# transponder-5_0.net
KiCad netlist of a schematic drawn in EAGLE
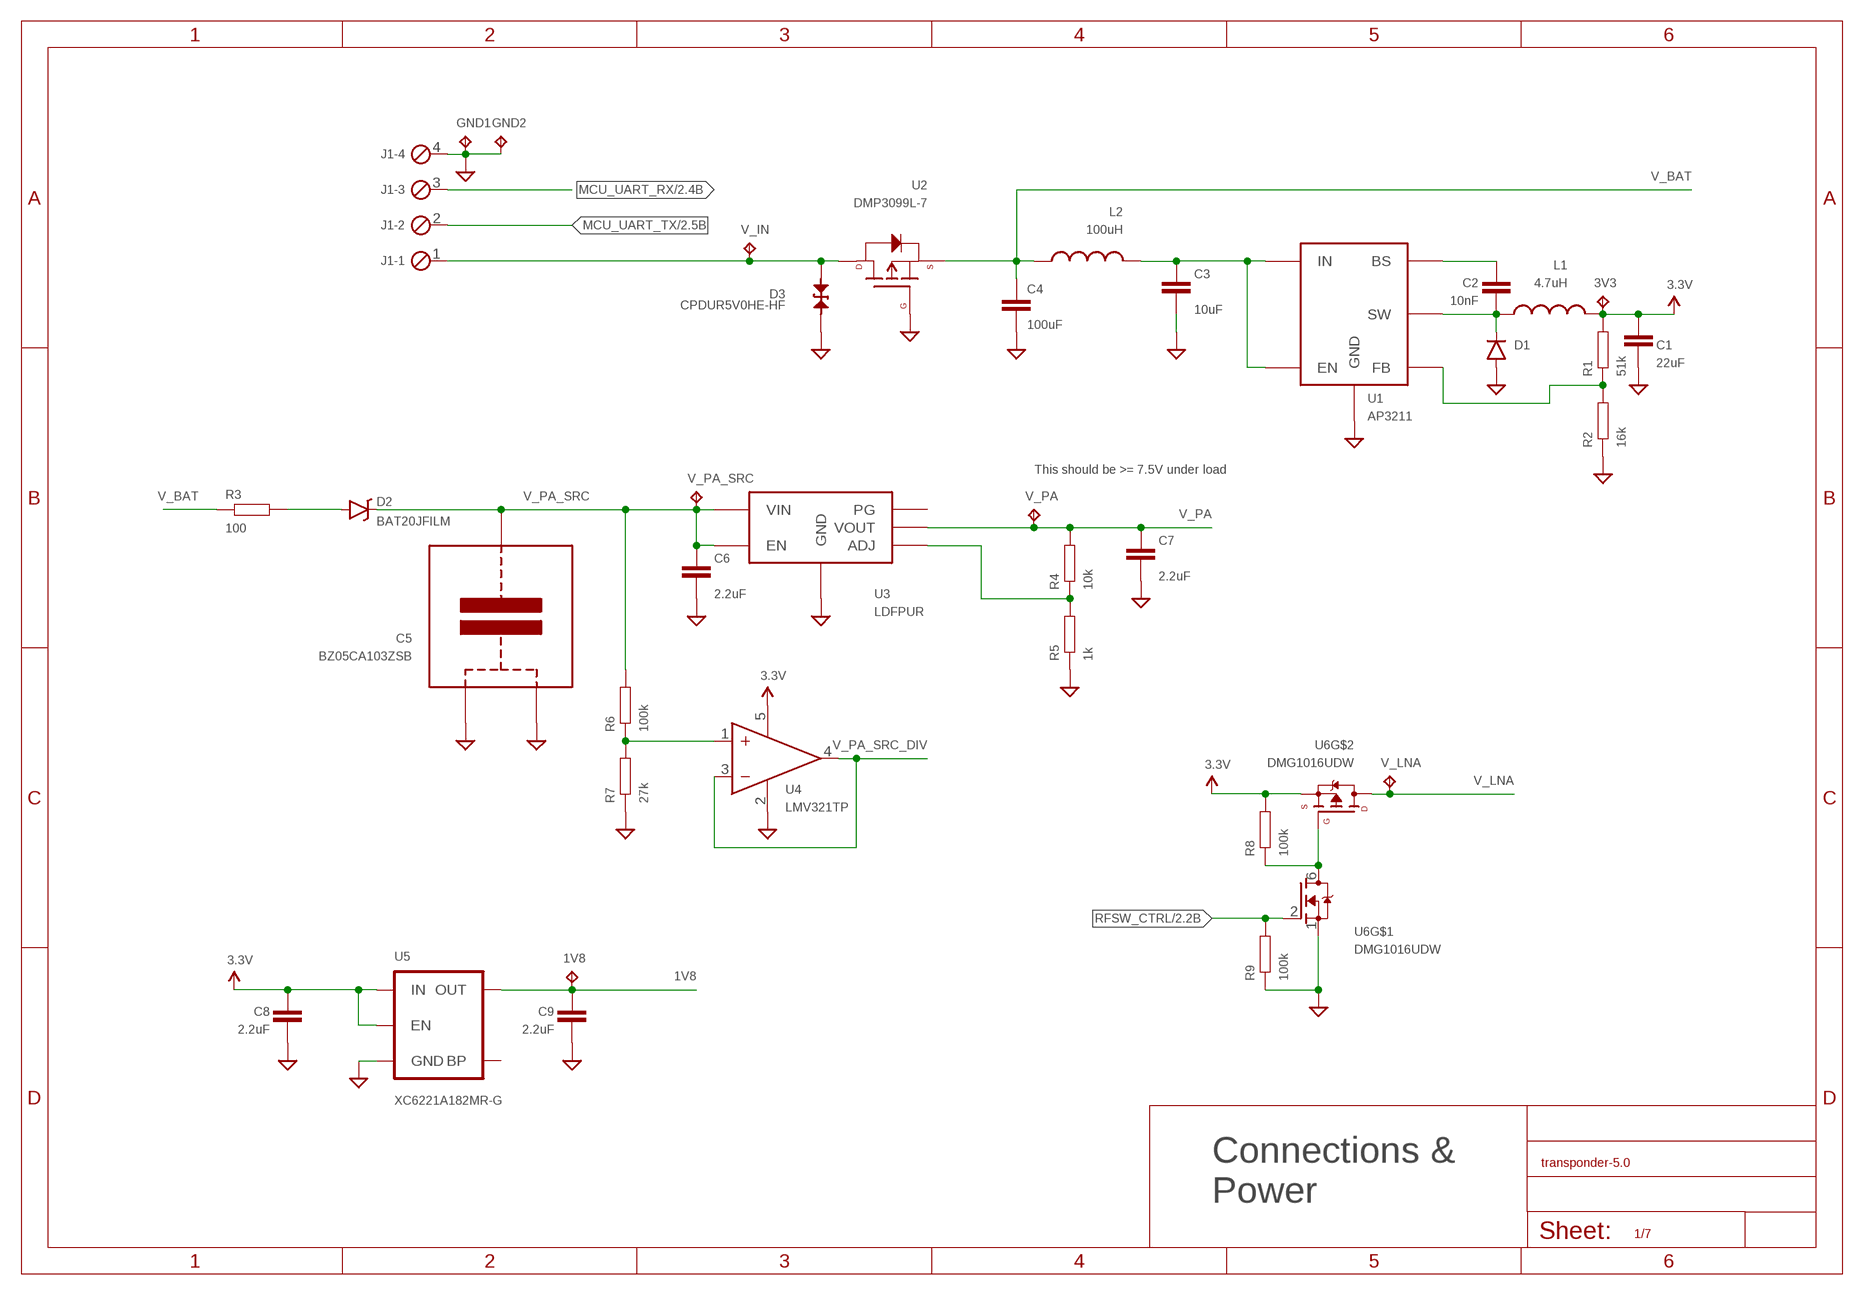
[diagram p0: schematic, sheet 1]
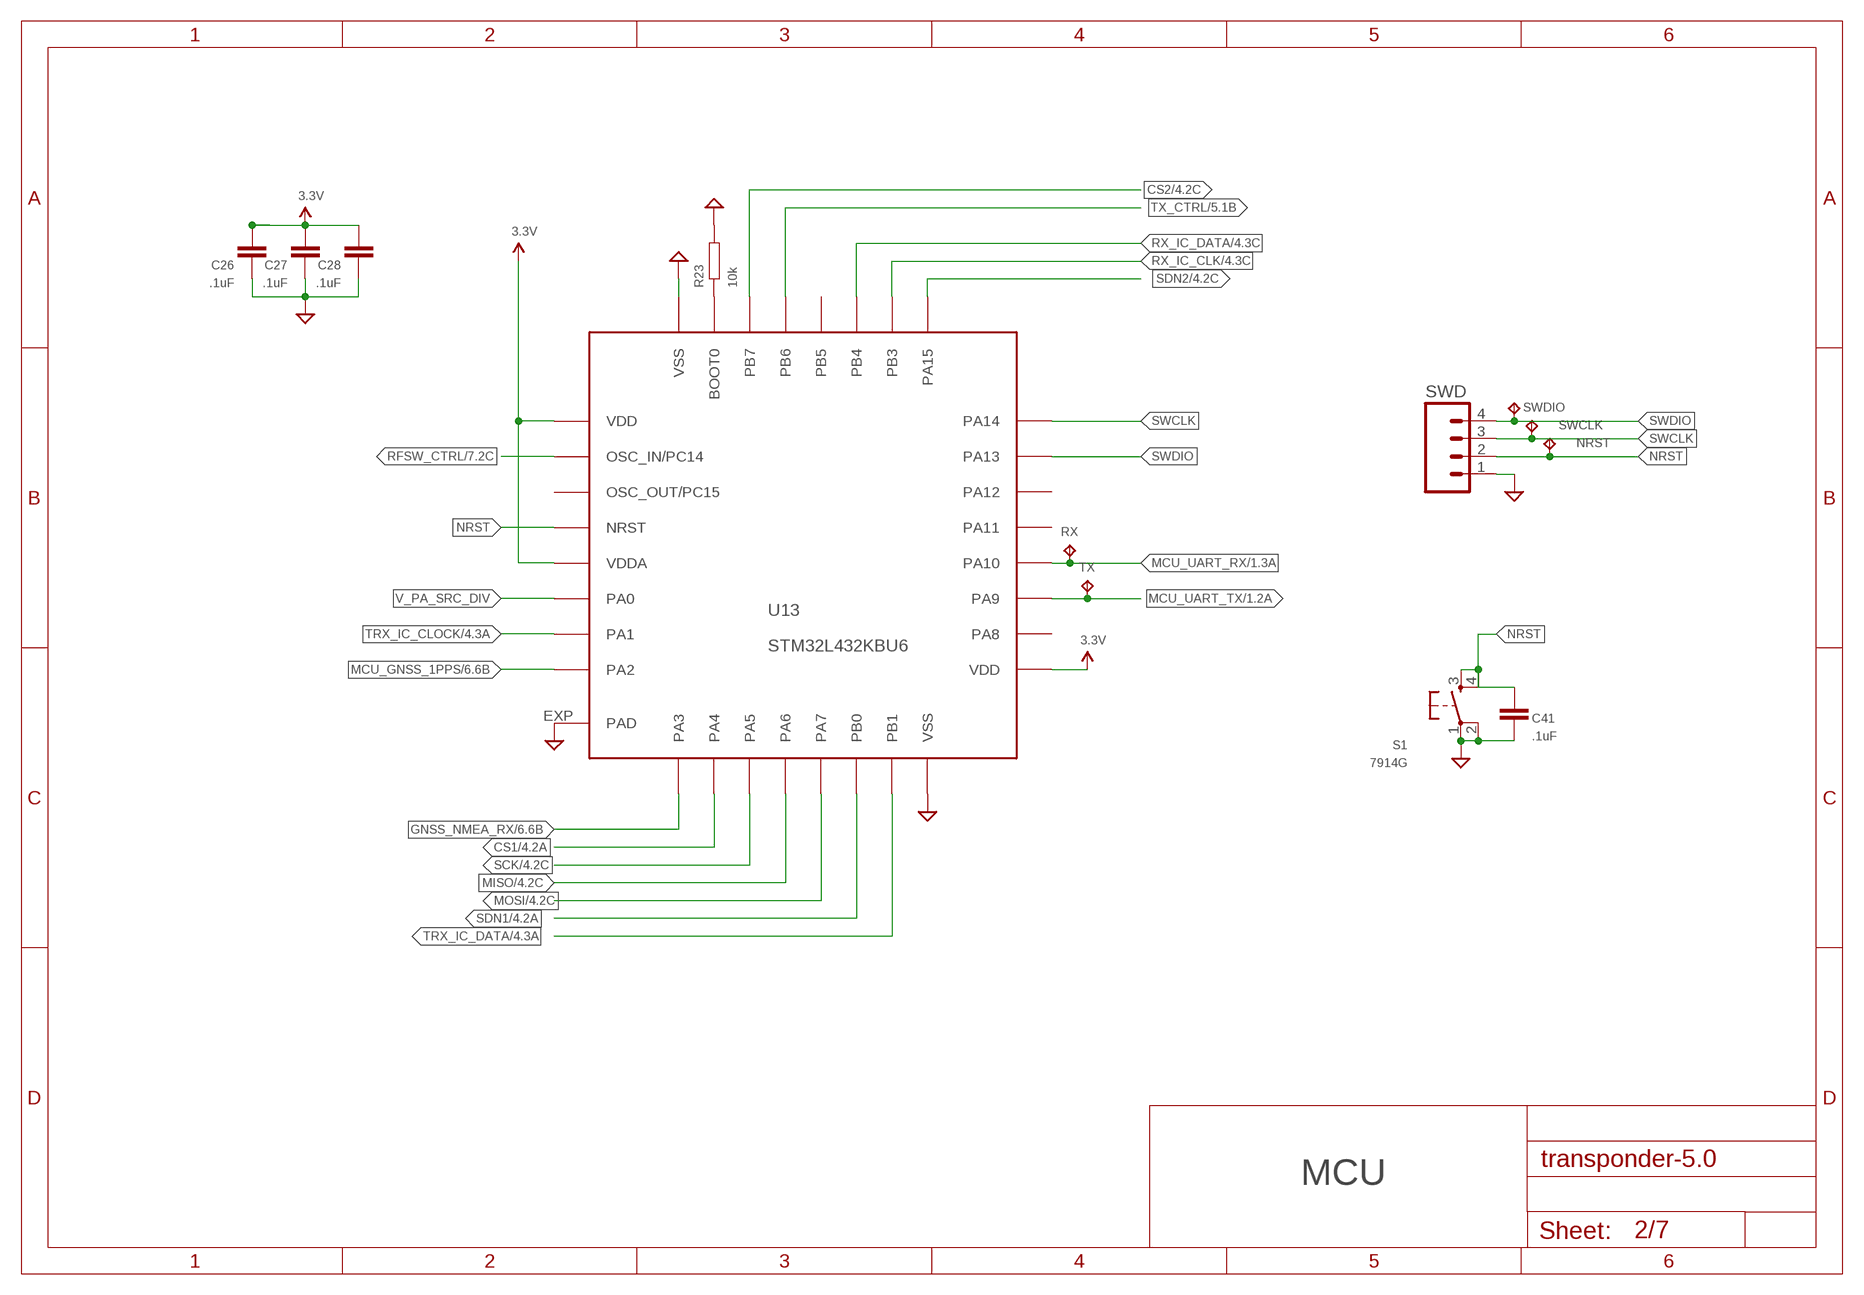
[diagram p1: schematic, sheet 2]
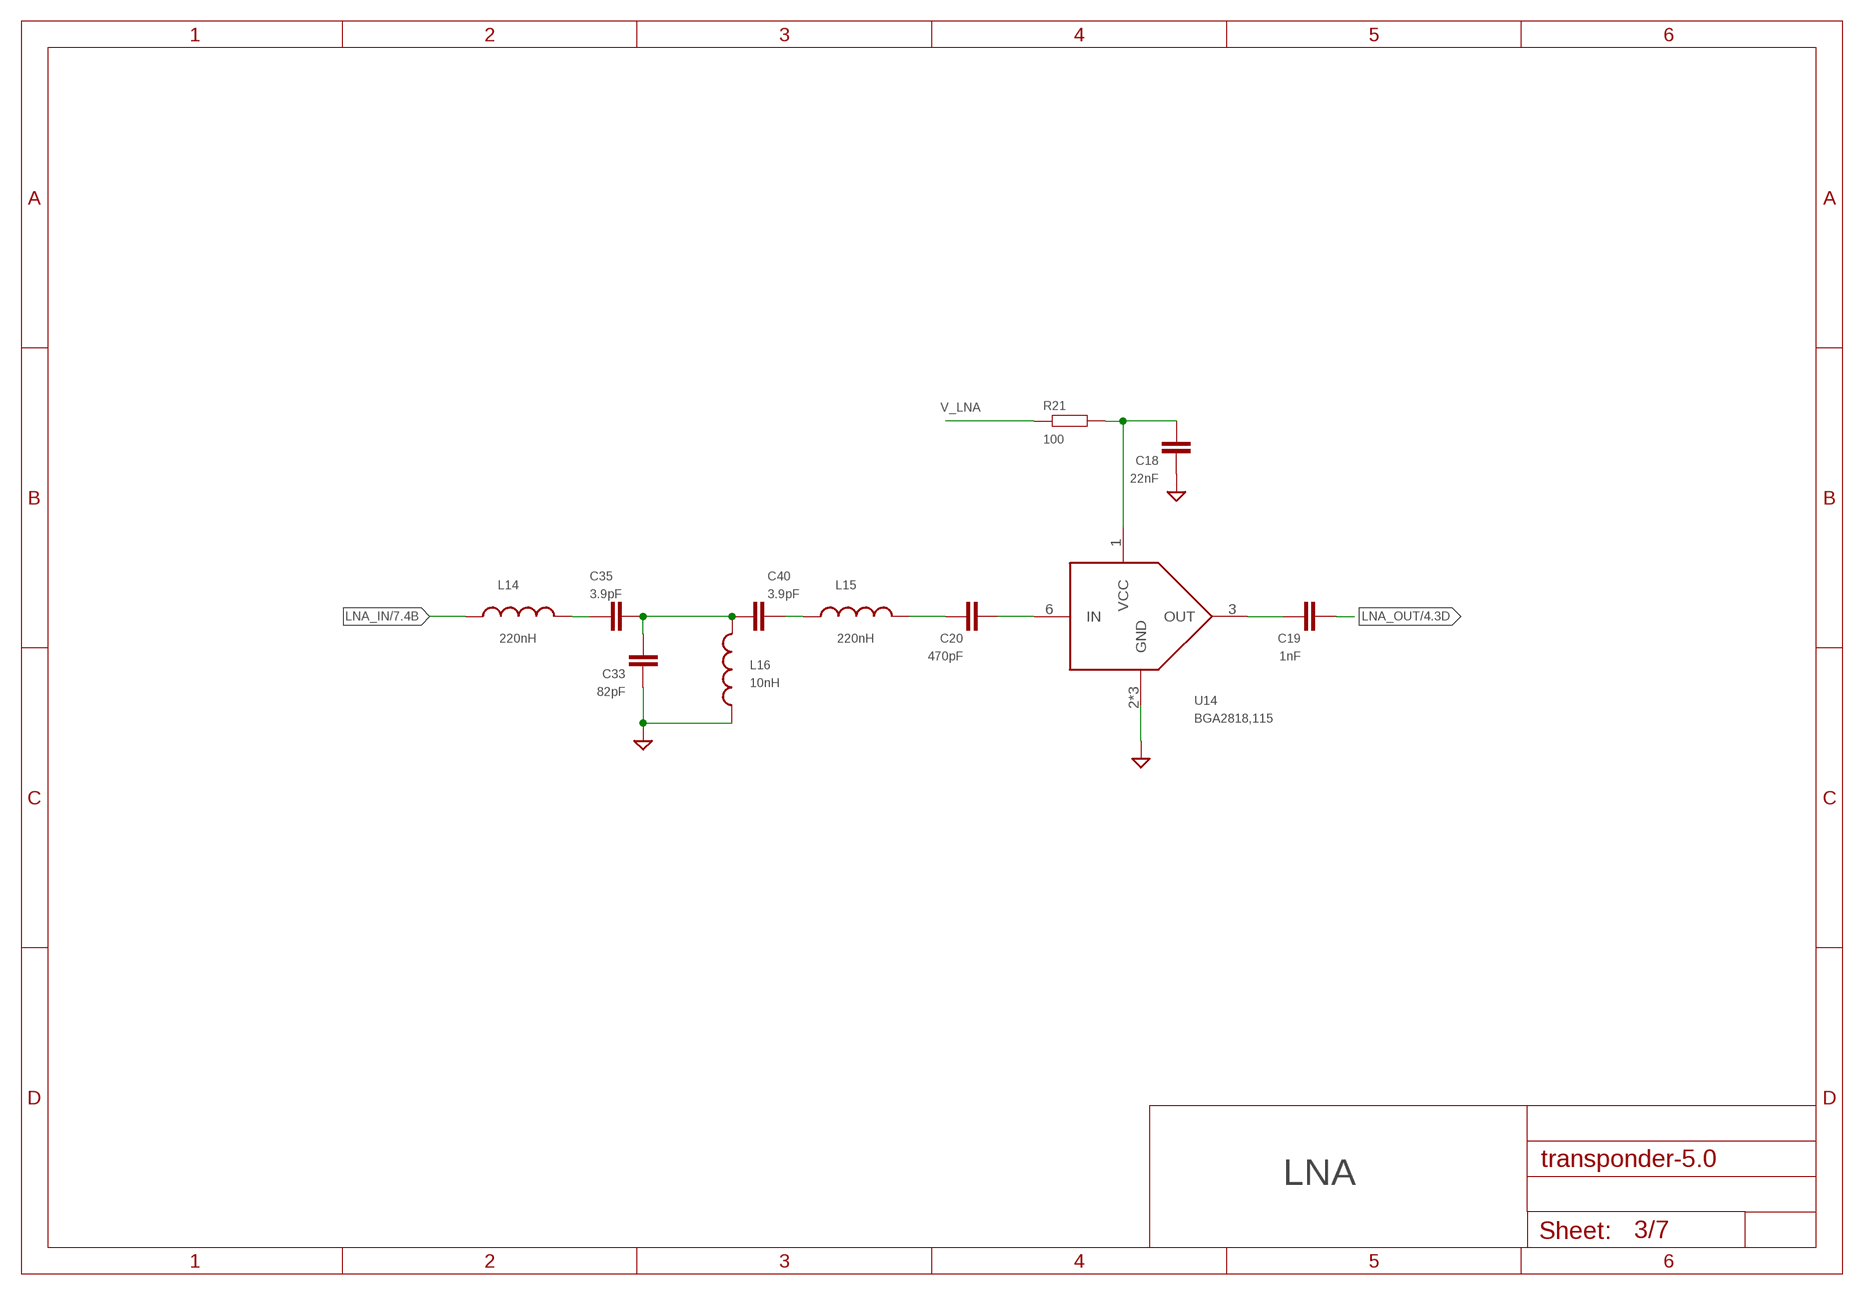
[diagram p2: schematic, sheet 3]
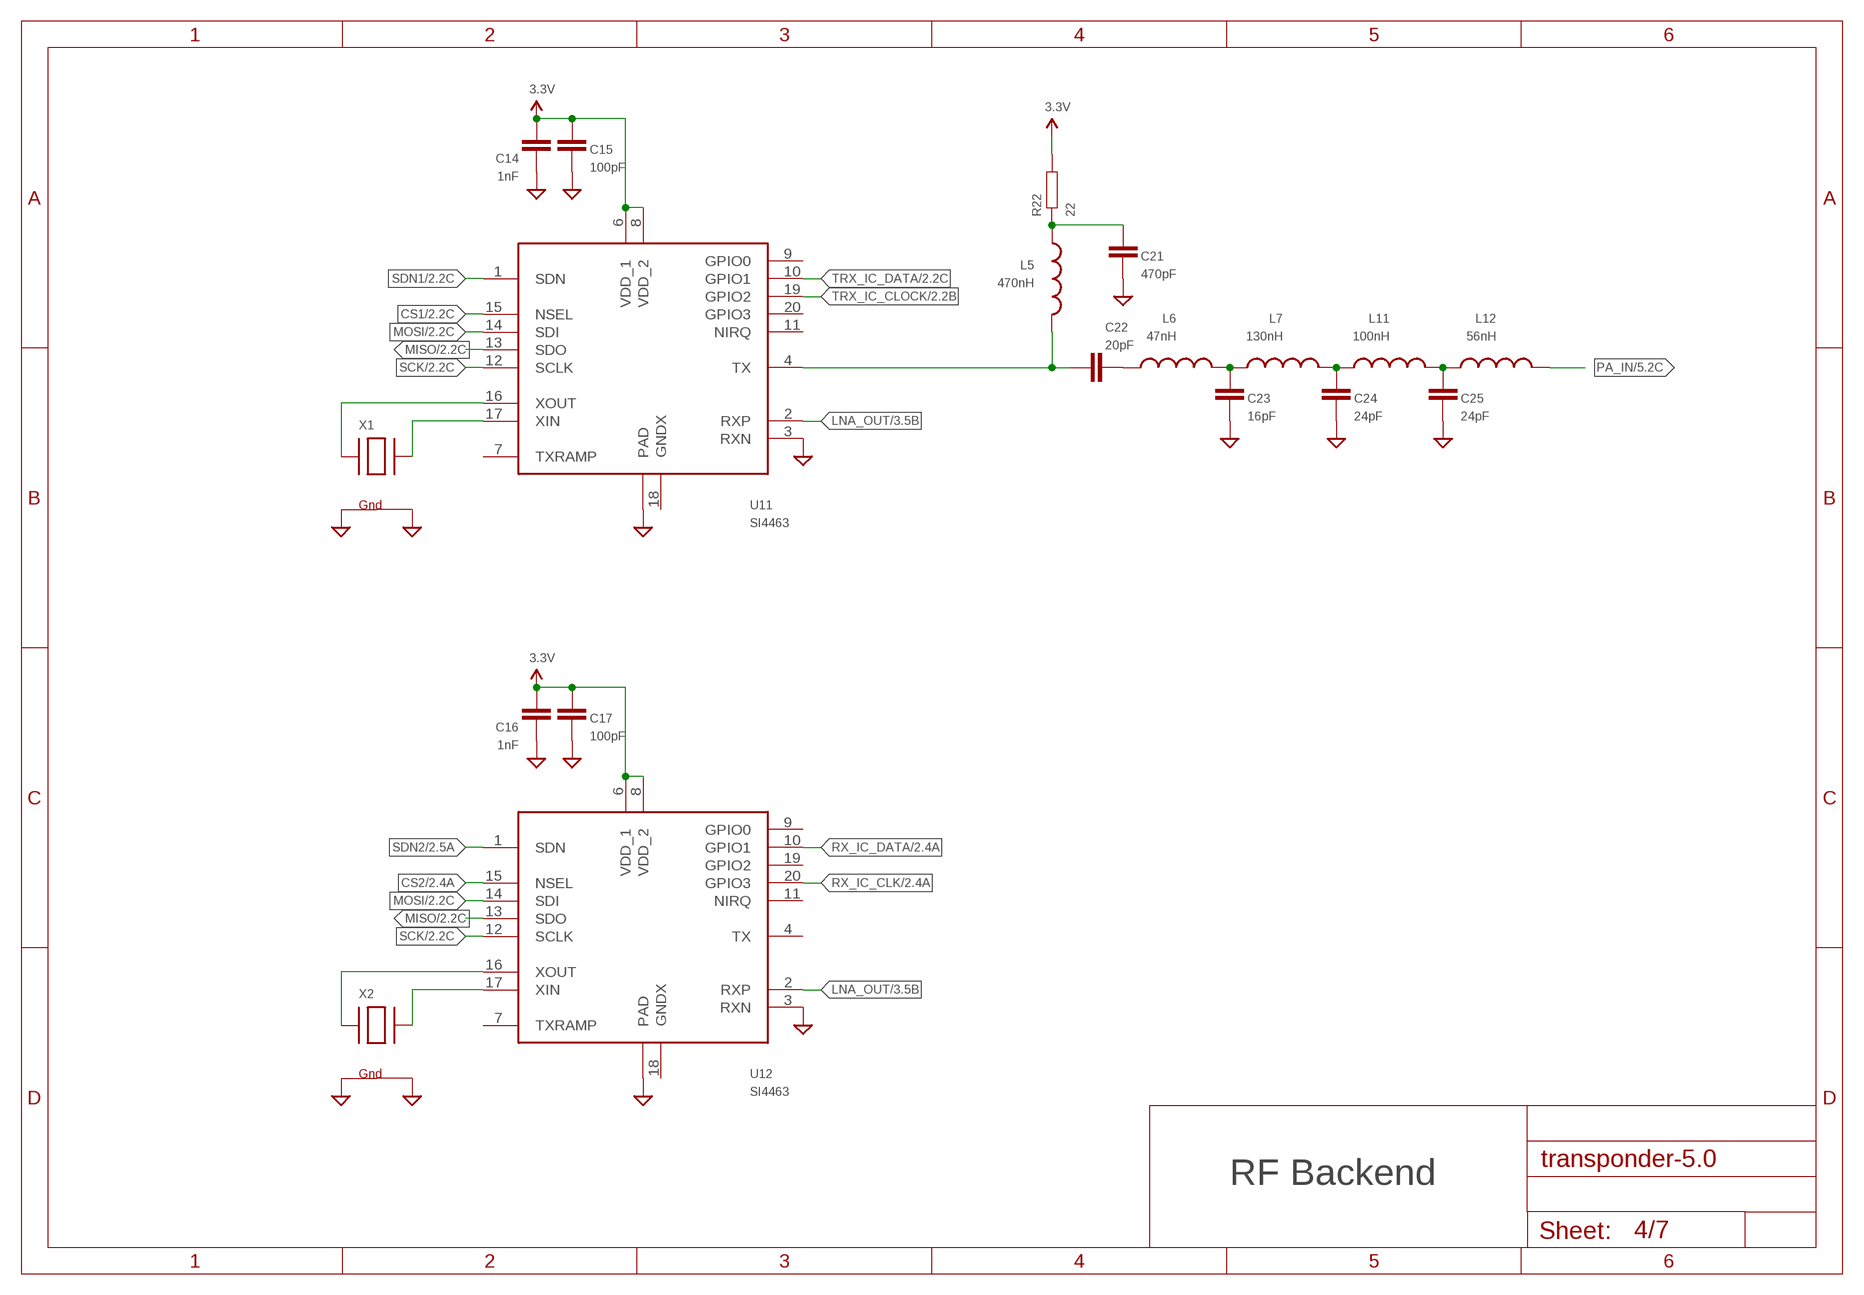
[diagram p3: schematic, sheet 4]
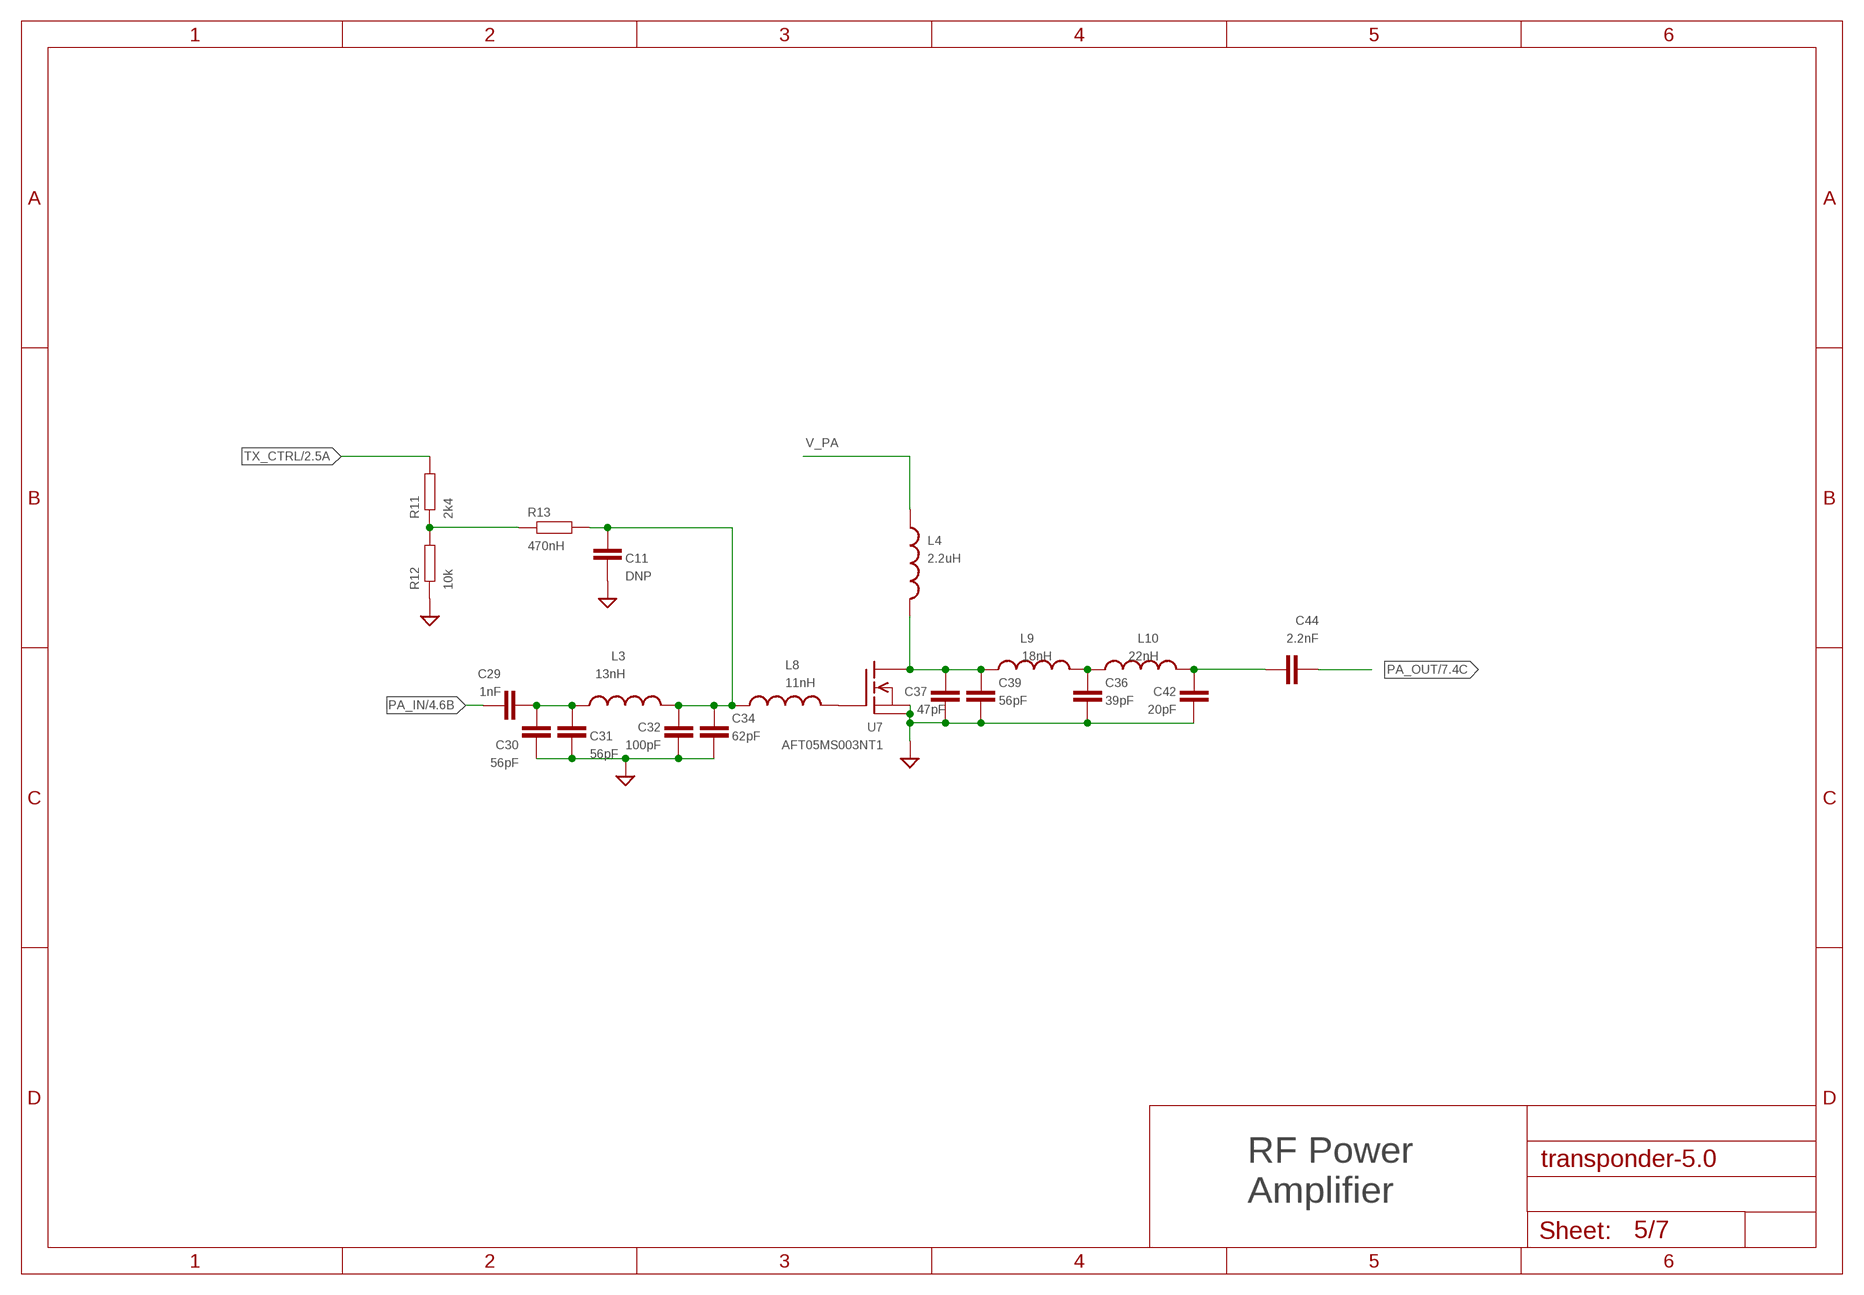
[diagram p4: schematic, sheet 5]
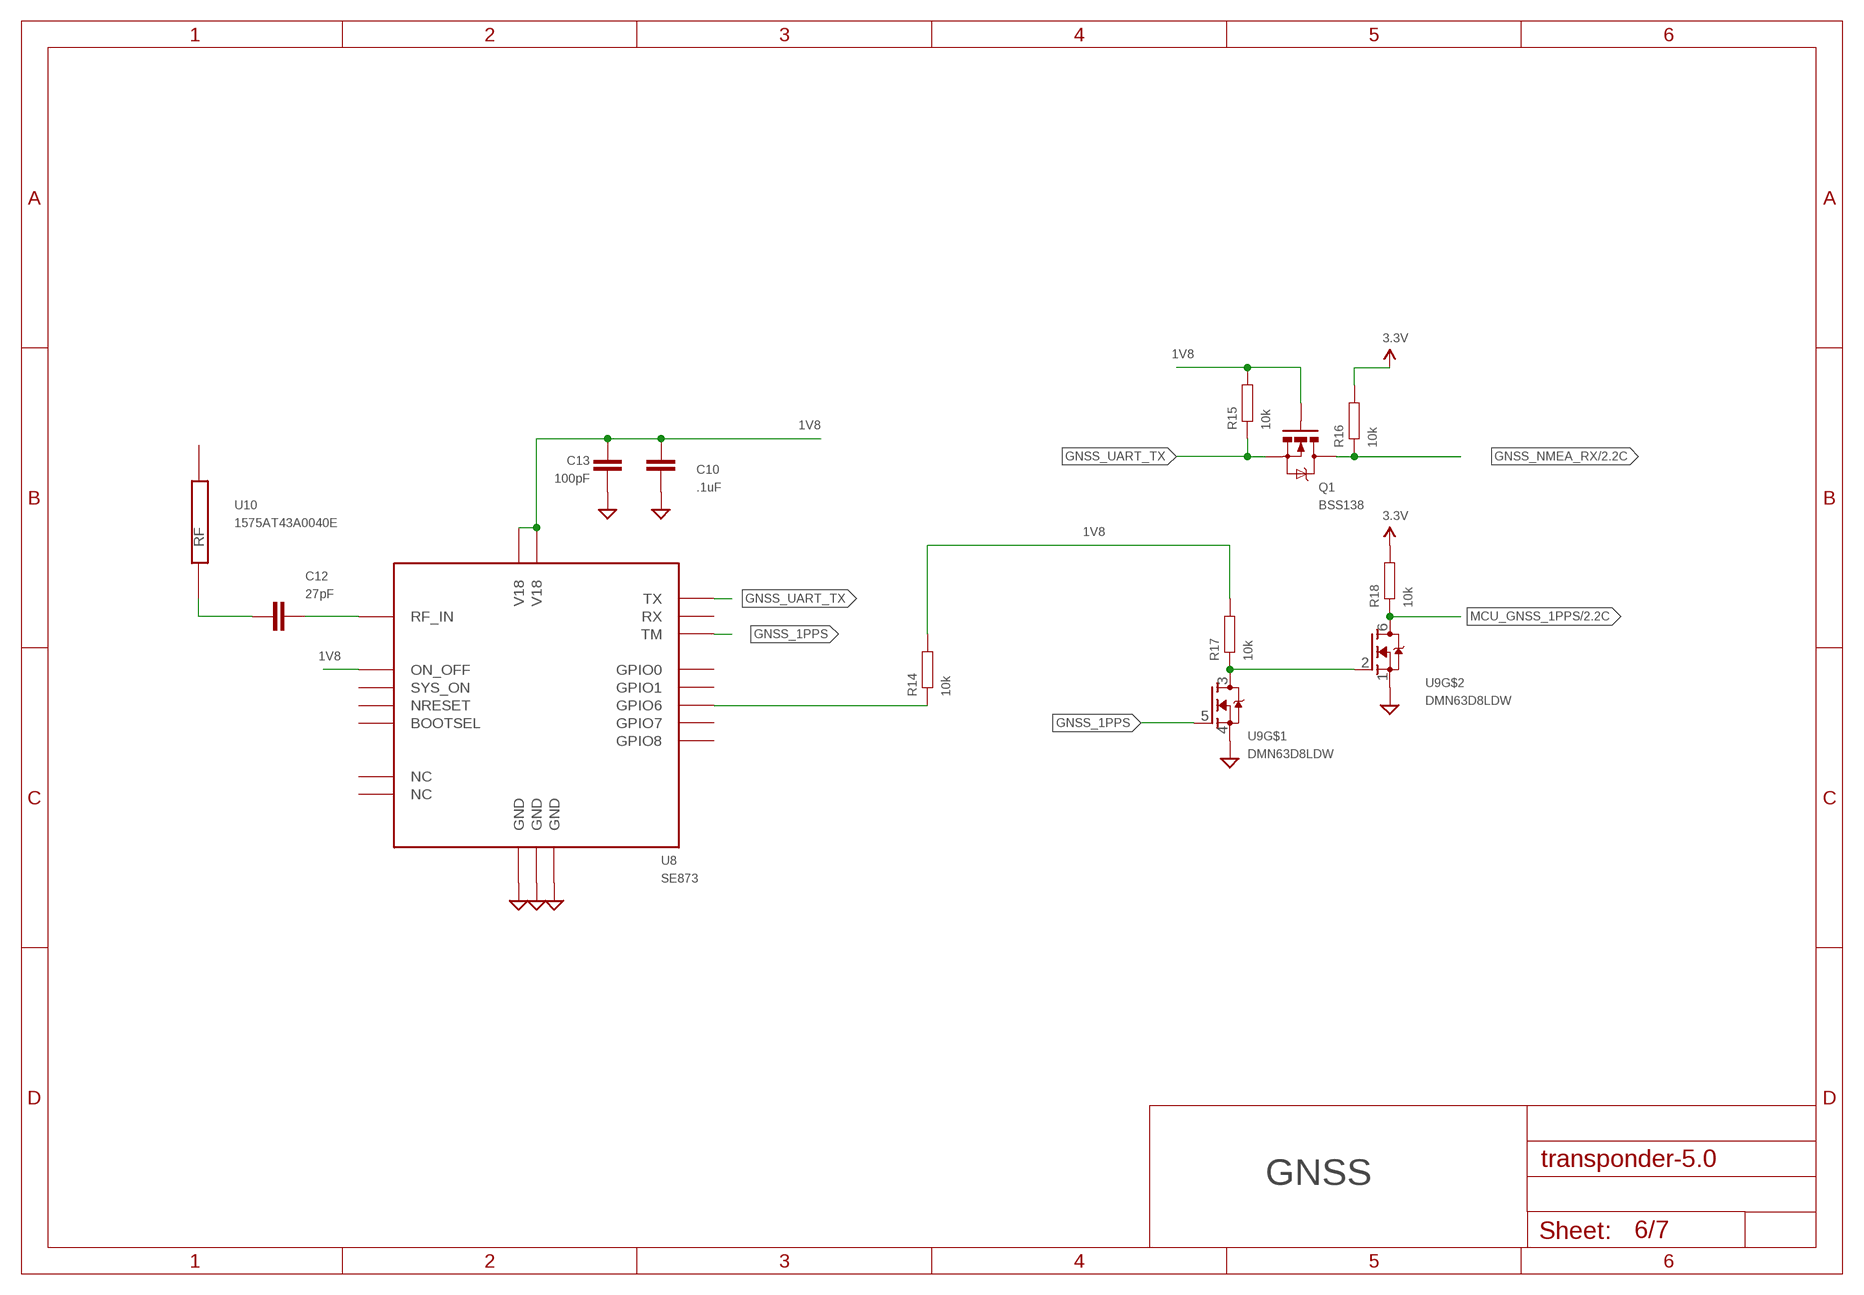
[diagram p5: schematic, sheet 6]
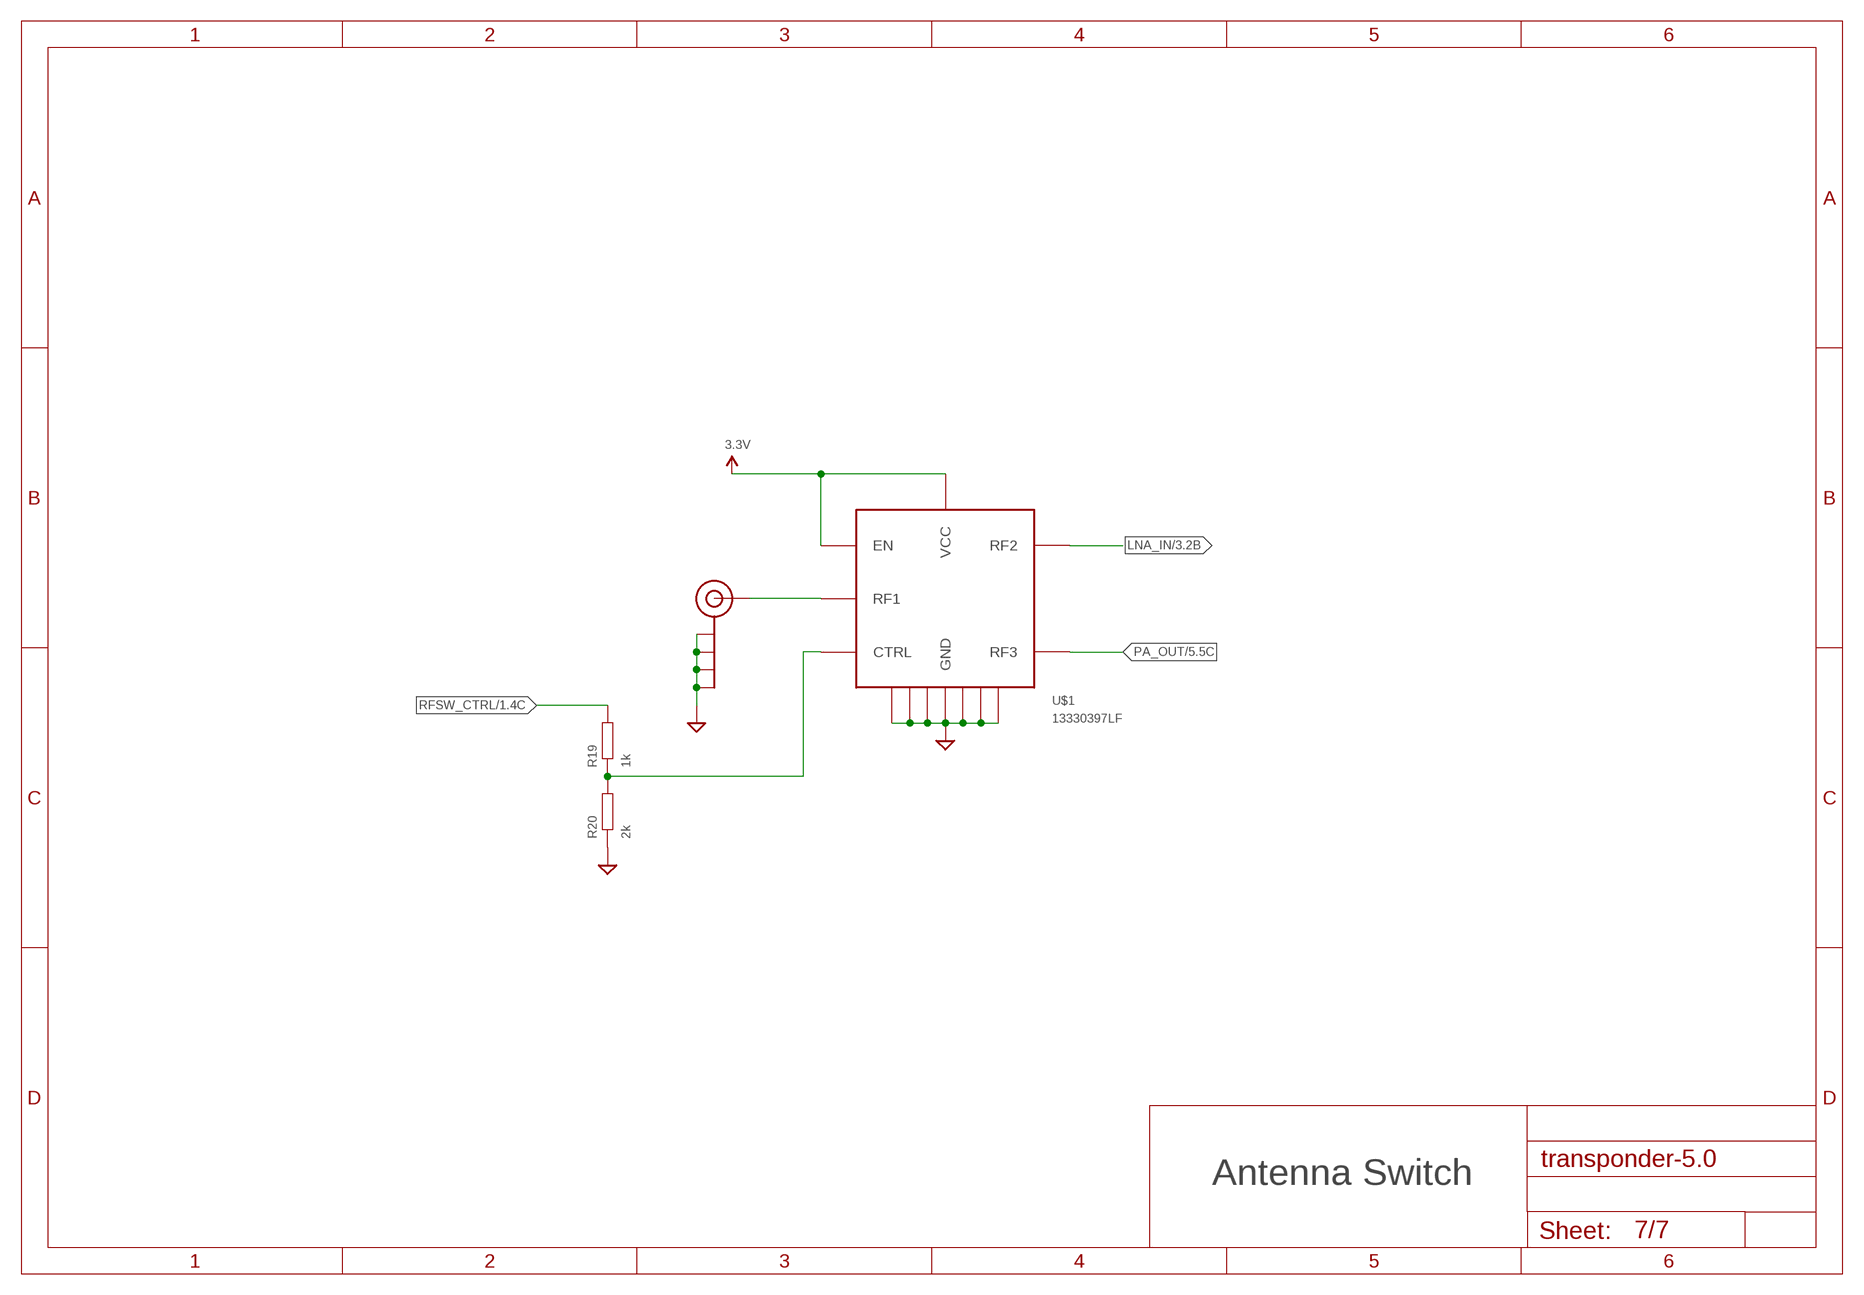
[diagram p6: schematic, sheet 7]

(export (version "E")
  (design (tool "Eeschema 10.0.6"))
  (components
    (comp (ref "J$1")
      (value "SMA_EDGE")
      (footprint "eagle-import:SMA-EDGE")
      (libsource (lib "eagle-import") (part "SMA_EDGE"))
    )
    (comp (ref "R19")
      (value "1k")
      (footprint "eagle-import:0603-RES")
      (libsource (lib "eagle-import") (part "RESISTOR0603-RES"))
    )
    (comp (ref "R20")
      (value "2k")
      (footprint "eagle-import:0603-RES")
      (libsource (lib "eagle-import") (part "RESISTOR0603-RES"))
    )
    (comp (ref "U$1")
      (value "13330397LF")
      (footprint "eagle-import:QFN12")
      (libsource (lib "eagle-import") (part "SKYWORKS-13330397LF"))
    )
    (comp (ref "C18")
      (value "22nF")
      (footprint "eagle-import:0603-CAP")
      (libsource (lib "eagle-import") (part "CAP0603-CAP"))
    )
    (comp (ref "C19")
      (value "1nF")
      (footprint "eagle-import:0603-CAP")
      (libsource (lib "eagle-import") (part "CAP0603-CAP"))
    )
    (comp (ref "C20")
      (value "470pF")
      (footprint "eagle-import:0603-CAP")
      (libsource (lib "eagle-import") (part "CAP0603-CAP"))
    )
    (comp (ref "C33")
      (value "82pF")
      (footprint "eagle-import:0603-CAP")
      (libsource (lib "eagle-import") (part "CAP0603-CAP"))
    )
    (comp (ref "C35")
      (value "3.9pF")
      (footprint "eagle-import:0603-CAP")
      (libsource (lib "eagle-import") (part "CAP0603-CAP"))
    )
    (comp (ref "C40")
      (value "3.9pF")
      (footprint "eagle-import:0603-CAP")
      (libsource (lib "eagle-import") (part "CAP0603-CAP"))
    )
    (comp (ref "L14")
      (value "220nH")
      (footprint "eagle-import:0603")
      (libsource (lib "eagle-import") (part "INDUCTOR0603"))
    )
    (comp (ref "L15")
      (value "220nH")
      (footprint "eagle-import:0603")
      (libsource (lib "eagle-import") (part "INDUCTOR0603"))
    )
    (comp (ref "L16")
      (value "10nH")
      (footprint "eagle-import:0603")
      (libsource (lib "eagle-import") (part "INDUCTOR0603"))
    )
    (comp (ref "R21")
      (value "100")
      (footprint "eagle-import:0603-RES")
      (libsource (lib "eagle-import") (part "RESISTOR0603-RES"))
    )
    (comp (ref "U14")
      (value "BGA2818,115")
      (footprint "eagle-import:SOT363")
      (libsource (lib "eagle-import") (part "BGA2870"))
    )
    (comp (ref "C26")
      (value ".1uF")
      (footprint "eagle-import:0603-CAP")
      (libsource (lib "eagle-import") (part "CAP0603-CAP"))
    )
    (comp (ref "C27")
      (value ".1uF")
      (footprint "eagle-import:0603-CAP")
      (libsource (lib "eagle-import") (part "CAP0603-CAP"))
    )
    (comp (ref "C28")
      (value ".1uF")
      (footprint "eagle-import:0603-CAP")
      (libsource (lib "eagle-import") (part "CAP0603-CAP"))
    )
    (comp (ref "C41")
      (value ".1uF")
      (footprint "eagle-import:0603-CAP")
      (libsource (lib "eagle-import") (part "CAP0603-CAP"))
    )
    (comp (ref "NRST")
      (value "TPTP12R")
      (footprint "eagle-import:TP12R")
      (libsource (lib "eagle-import") (part "TPTP12R"))
    )
    (comp (ref "R23")
      (value "10k")
      (footprint "eagle-import:0603-RES")
      (libsource (lib "eagle-import") (part "RESISTOR0603-RES"))
    )
    (comp (ref "RX")
      (value "TPTP12R")
      (footprint "eagle-import:TP12R")
      (libsource (lib "eagle-import") (part "TPTP12R"))
    )
    (comp (ref "S1")
      (value "7914G")
      (footprint "eagle-import:7914G")
      (libsource (lib "eagle-import") (part "TACTILE-SWITCH-7914G"))
    )
    (comp (ref "SWCLK")
      (value "TPTP12R")
      (footprint "eagle-import:TP12R")
      (libsource (lib "eagle-import") (part "TPTP12R"))
    )
    (comp (ref "SWD")
      (value "M04PTH")
      (footprint "eagle-import:1X04")
      (libsource (lib "eagle-import") (part "M04PTH"))
    )
    (comp (ref "SWDIO")
      (value "TPTP12R")
      (footprint "eagle-import:TP12R")
      (libsource (lib "eagle-import") (part "TPTP12R"))
    )
    (comp (ref "TX")
      (value "TPTP12R")
      (footprint "eagle-import:TP12R")
      (libsource (lib "eagle-import") (part "TPTP12R"))
    )
    (comp (ref "U13")
      (value "STM32L432KBU6")
      (footprint "eagle-import:QFN32")
      (libsource (lib "eagle-import") (part "STM32L432KXXX"))
    )
    (comp (ref "C14")
      (value "1nF")
      (footprint "eagle-import:0603-CAP")
      (libsource (lib "eagle-import") (part "CAP0603-CAP"))
    )
    (comp (ref "C15")
      (value "100pF")
      (footprint "eagle-import:0603-CAP")
      (libsource (lib "eagle-import") (part "CAP0603-CAP"))
    )
    (comp (ref "C16")
      (value "1nF")
      (footprint "eagle-import:0603-CAP")
      (libsource (lib "eagle-import") (part "CAP0603-CAP"))
    )
    (comp (ref "C17")
      (value "100pF")
      (footprint "eagle-import:0603-CAP")
      (libsource (lib "eagle-import") (part "CAP0603-CAP"))
    )
    (comp (ref "C21")
      (value "470pF")
      (footprint "eagle-import:0603-CAP")
      (libsource (lib "eagle-import") (part "CAP0603-CAP"))
    )
    (comp (ref "C22")
      (value "20pF")
      (footprint "eagle-import:0603-CAP")
      (libsource (lib "eagle-import") (part "CAP0603-CAP"))
    )
    (comp (ref "C23")
      (value "16pF")
      (footprint "eagle-import:0603-CAP")
      (libsource (lib "eagle-import") (part "CAP0603-CAP"))
    )
    (comp (ref "C24")
      (value "24pF")
      (footprint "eagle-import:0603-CAP")
      (libsource (lib "eagle-import") (part "CAP0603-CAP"))
    )
    (comp (ref "C25")
      (value "24pF")
      (footprint "eagle-import:0603-CAP")
      (libsource (lib "eagle-import") (part "CAP0603-CAP"))
    )
    (comp (ref "L5")
      (value "470nH")
      (footprint "eagle-import:0603")
      (libsource (lib "eagle-import") (part "INDUCTOR0603"))
    )
    (comp (ref "L6")
      (value "47nH")
      (footprint "eagle-import:0603")
      (libsource (lib "eagle-import") (part "INDUCTOR0603"))
    )
    (comp (ref "L7")
      (value "130nH")
      (footprint "eagle-import:0603")
      (libsource (lib "eagle-import") (part "INDUCTOR0603"))
    )
    (comp (ref "L11")
      (value "100nH")
      (footprint "eagle-import:0603")
      (libsource (lib "eagle-import") (part "INDUCTOR0603"))
    )
    (comp (ref "L12")
      (value "56nH")
      (footprint "eagle-import:0603")
      (libsource (lib "eagle-import") (part "INDUCTOR0603"))
    )
    (comp (ref "R22")
      (value "22")
      (footprint "eagle-import:0603-RES")
      (libsource (lib "eagle-import") (part "RESISTOR0603-RES"))
    )
    (comp (ref "U11")
      (value "SI4463")
      (footprint "eagle-import:SI4463")
      (libsource (lib "eagle-import") (part "SI4463"))
    )
    (comp (ref "U12")
      (value "SI4463")
      (footprint "eagle-import:SI4463")
      (libsource (lib "eagle-import") (part "SI4463"))
    )
    (comp (ref "X1")
      (value "XTAL-4-3225")
      (footprint "eagle-import:NX3225")
      (libsource (lib "eagle-import") (part "XTAL-4-3225"))
    )
    (comp (ref "X2")
      (value "XTAL-4-3225")
      (footprint "eagle-import:NX3225")
      (libsource (lib "eagle-import") (part "XTAL-4-3225"))
    )
    (comp (ref "C10")
      (value ".1uF")
      (footprint "eagle-import:0603-CAP")
      (libsource (lib "eagle-import") (part "CAP0603-CAP"))
    )
    (comp (ref "C12")
      (value "27pF")
      (footprint "eagle-import:0603-CAP")
      (libsource (lib "eagle-import") (part "CAP0603-CAP"))
    )
    (comp (ref "C13")
      (value "100pF")
      (footprint "eagle-import:0603-CAP")
      (libsource (lib "eagle-import") (part "CAP0603-CAP"))
    )
    (comp (ref "Q1")
      (value "BSS138")
      (footprint "eagle-import:SOT23-3")
      (libsource (lib "eagle-import") (part "MOSFET-NCHANNELBSS138"))
    )
    (comp (ref "R14")
      (value "10k")
      (footprint "eagle-import:0603-RES")
      (libsource (lib "eagle-import") (part "RESISTOR0603-RES"))
    )
    (comp (ref "R15")
      (value "10k")
      (footprint "eagle-import:0603-RES")
      (libsource (lib "eagle-import") (part "RESISTOR0603-RES"))
    )
    (comp (ref "R16")
      (value "10k")
      (footprint "eagle-import:0603-RES")
      (libsource (lib "eagle-import") (part "RESISTOR0603-RES"))
    )
    (comp (ref "R17")
      (value "10k")
      (footprint "eagle-import:0603-RES")
      (libsource (lib "eagle-import") (part "RESISTOR0603-RES"))
    )
    (comp (ref "R18")
      (value "10k")
      (footprint "eagle-import:0603-RES")
      (libsource (lib "eagle-import") (part "RESISTOR0603-RES"))
    )
    (comp (ref "U8")
      (value "SE873")
      (footprint "eagle-import:SE873")
      (libsource (lib "eagle-import") (part "SE873"))
    )
    (comp (ref "U9")
      (value "DMN63D8LDW")
      (footprint "eagle-import:SOT363")
      (libsource (lib "eagle-import") (part "DMN63D8LDW"))
    )
    (comp (ref "U10")
      (value "1575AT43A0040E")
      (footprint "eagle-import:1575AT43A0040E")
      (libsource (lib "eagle-import") (part "1575AT43A0040E"))
    )
    (comp (ref "C11")
      (value "DNP")
      (footprint "eagle-import:0603-CAP")
      (libsource (lib "eagle-import") (part "CAP0603-CAP"))
    )
    (comp (ref "C29")
      (value "1nF")
      (footprint "eagle-import:0603-CAP")
      (libsource (lib "eagle-import") (part "CAP0603-CAP"))
    )
    (comp (ref "C30")
      (value "56pF")
      (footprint "eagle-import:0603-CAP")
      (libsource (lib "eagle-import") (part "CAP0603-CAP"))
    )
    (comp (ref "C31")
      (value "56pF")
      (footprint "eagle-import:0603-CAP")
      (libsource (lib "eagle-import") (part "CAP0603-CAP"))
    )
    (comp (ref "C32")
      (value "100pF")
      (footprint "eagle-import:0603-CAP")
      (libsource (lib "eagle-import") (part "CAP0603-CAP"))
    )
    (comp (ref "C34")
      (value "62pF")
      (footprint "eagle-import:0603-CAP")
      (libsource (lib "eagle-import") (part "CAP0603-CAP"))
    )
    (comp (ref "C36")
      (value "39pF")
      (footprint "eagle-import:0805")
      (libsource (lib "eagle-import") (part "CAP0805"))
    )
    (comp (ref "C37")
      (value "47pF")
      (footprint "eagle-import:0805")
      (libsource (lib "eagle-import") (part "CAP0805"))
    )
    (comp (ref "C39")
      (value "56pF")
      (footprint "eagle-import:0805")
      (libsource (lib "eagle-import") (part "CAP0805"))
    )
    (comp (ref "C42")
      (value "20pF")
      (footprint "eagle-import:0805")
      (libsource (lib "eagle-import") (part "CAP0805"))
    )
    (comp (ref "C44")
      (value "2.2nF")
      (footprint "eagle-import:0805")
      (libsource (lib "eagle-import") (part "CAP0805"))
    )
    (comp (ref "L3")
      (value "13nH")
      (footprint "eagle-import:0603")
      (libsource (lib "eagle-import") (part "INDUCTOR0603"))
    )
    (comp (ref "L4")
      (value "2.2uH")
      (footprint "eagle-import:0805")
      (libsource (lib "eagle-import") (part "INDUCTOR0805"))
    )
    (comp (ref "L8")
      (value "11nH")
      (footprint "eagle-import:0603")
      (libsource (lib "eagle-import") (part "INDUCTOR0603"))
    )
    (comp (ref "L9")
      (value "18nH")
      (footprint "eagle-import:0805")
      (libsource (lib "eagle-import") (part "INDUCTOR0805"))
    )
    (comp (ref "L10")
      (value "22nH")
      (footprint "eagle-import:0805")
      (libsource (lib "eagle-import") (part "INDUCTOR0805"))
    )
    (comp (ref "R11")
      (value "2k4")
      (footprint "eagle-import:0603-RES")
      (libsource (lib "eagle-import") (part "RESISTOR0603-RES"))
    )
    (comp (ref "R12")
      (value "10k")
      (footprint "eagle-import:0603-RES")
      (libsource (lib "eagle-import") (part "RESISTOR0603-RES"))
    )
    (comp (ref "R13")
      (value "470nH")
      (footprint "eagle-import:0603-RES")
      (libsource (lib "eagle-import") (part "RESISTOR0603-RES"))
    )
    (comp (ref "U7")
      (value "AFT05MS003NT1")
      (footprint "eagle-import:SOT-89")
      (libsource (lib "eagle-import") (part "AFT0SMS003N"))
    )
    (comp (ref "1V8")
      (value "TPTP12R")
      (footprint "eagle-import:TP12R")
      (libsource (lib "eagle-import") (part "TPTP12R"))
    )
    (comp (ref "3V3")
      (value "TPTP12R")
      (footprint "eagle-import:TP12R")
      (libsource (lib "eagle-import") (part "TPTP12R"))
    )
    (comp (ref "C1")
      (value "22uF")
      (footprint "eagle-import:0805")
      (libsource (lib "eagle-import") (part "CAP0805"))
    )
    (comp (ref "C2")
      (value "10nF")
      (footprint "eagle-import:0603-CAP")
      (libsource (lib "eagle-import") (part "CAP0603-CAP"))
    )
    (comp (ref "C3")
      (value "10uF")
      (footprint "eagle-import:0805")
      (libsource (lib "eagle-import") (part "CAP0805"))
    )
    (comp (ref "C4")
      (value "100uF")
      (footprint "eagle-import:1210")
      (libsource (lib "eagle-import") (part "CAP1210"))
    )
    (comp (ref "C5")
      (value "BZ05CA103ZSB")
      (footprint "eagle-import:BZ05")
      (libsource (lib "eagle-import") (part "BZ05CA103ZSB"))
    )
    (comp (ref "C6")
      (value "2.2uF")
      (footprint "eagle-import:0603-CAP")
      (libsource (lib "eagle-import") (part "CAP0603-CAP"))
    )
    (comp (ref "C7")
      (value "2.2uF")
      (footprint "eagle-import:0603-CAP")
      (libsource (lib "eagle-import") (part "CAP0603-CAP"))
    )
    (comp (ref "C8")
      (value "2.2uF")
      (footprint "eagle-import:0603-CAP")
      (libsource (lib "eagle-import") (part "CAP0603-CAP"))
    )
    (comp (ref "C9")
      (value "2.2uF")
      (footprint "eagle-import:0603-CAP")
      (libsource (lib "eagle-import") (part "CAP0603-CAP"))
    )
    (comp (ref "D1")
      (value "DIODESOD123")
      (footprint "eagle-import:SOD-123")
      (libsource (lib "eagle-import") (part "DIODESOD123"))
    )
    (comp (ref "D2")
      (value "BAT20JFILM")
      (footprint "eagle-import:SOD-323")
      (libsource (lib "eagle-import") (part "BAT20JFILM"))
    )
    (comp (ref "D3")
      (value "CPDUR5V0HE-HF")
      (footprint "eagle-import:0603")
      (libsource (lib "eagle-import") (part "CPDUR5V0HE-HF"))
    )
    (comp (ref "GND1")
      (value "TPTP12R")
      (footprint "eagle-import:TP12R")
      (libsource (lib "eagle-import") (part "TPTP12R"))
    )
    (comp (ref "GND2")
      (value "TPTP12R")
      (footprint "eagle-import:TP12R")
      (libsource (lib "eagle-import") (part "TPTP12R"))
    )
    (comp (ref "J1")
      (value "MPT4")
      (footprint "eagle-import:4POL254")
      (libsource (lib "eagle-import") (part "MPT4"))
    )
    (comp (ref "L1")
      (value "4.7uH")
      (footprint "eagle-import:0805")
      (libsource (lib "eagle-import") (part "INDUCTOR0805"))
    )
    (comp (ref "L2")
      (value "100uH")
      (footprint "eagle-import:1007")
      (libsource (lib "eagle-import") (part "INDUCTOR1007"))
    )
    (comp (ref "R1")
      (value "51k")
      (footprint "eagle-import:0603-RES")
      (libsource (lib "eagle-import") (part "RESISTOR0603-RES"))
    )
    (comp (ref "R2")
      (value "16k")
      (footprint "eagle-import:0603-RES")
      (libsource (lib "eagle-import") (part "RESISTOR0603-RES"))
    )
    (comp (ref "R3")
      (value "100")
      (footprint "eagle-import:0603-RES")
      (libsource (lib "eagle-import") (part "RESISTOR0603-RES"))
    )
    (comp (ref "R4")
      (value "10k")
      (footprint "eagle-import:0603-RES")
      (libsource (lib "eagle-import") (part "RESISTOR0603-RES"))
    )
    (comp (ref "R5")
      (value "1k")
      (footprint "eagle-import:0603-RES")
      (libsource (lib "eagle-import") (part "RESISTOR0603-RES"))
    )
    (comp (ref "R6")
      (value "100k")
      (footprint "eagle-import:0603-RES")
      (libsource (lib "eagle-import") (part "RESISTOR0603-RES"))
    )
    (comp (ref "R7")
      (value "27k")
      (footprint "eagle-import:0603-RES")
      (libsource (lib "eagle-import") (part "RESISTOR0603-RES"))
    )
    (comp (ref "R8")
      (value "100k")
      (footprint "eagle-import:0603-RES")
      (libsource (lib "eagle-import") (part "RESISTOR0603-RES"))
    )
    (comp (ref "R9")
      (value "100k")
      (footprint "eagle-import:0603-RES")
      (libsource (lib "eagle-import") (part "RESISTOR0603-RES"))
    )
    (comp (ref "U1")
      (value "AP3211")
      (footprint "eagle-import:SOT23-6")
      (libsource (lib "eagle-import") (part "AP3211"))
    )
    (comp (ref "U2")
      (value "DMP3099L-7")
      (footprint "eagle-import:SOT23-3")
      (libsource (lib "eagle-import") (part "P-CHANNEL-MOSFET"))
    )
    (comp (ref "U3")
      (value "LDFPUR")
      (footprint "eagle-import:DFN-6")
      (libsource (lib "eagle-import") (part "LDF"))
    )
    (comp (ref "U4")
      (value "LMV321TP")
      (footprint "eagle-import:SOT23-5")
      (libsource (lib "eagle-import") (part "LMV321TP"))
    )
    (comp (ref "U5")
      (value "XC6221A182MR-G")
      (footprint "eagle-import:SOT23-5")
      (libsource (lib "eagle-import") (part "V_REG_LDOSMD"))
    )
    (comp (ref "U6")
      (value "DMG1016UDW")
      (footprint "eagle-import:SOT363")
      (libsource (lib "eagle-import") (part "DMG1016UDW"))
    )
    (comp (ref "V_IN")
      (value "TPTP12R")
      (footprint "eagle-import:TP12R")
      (libsource (lib "eagle-import") (part "TPTP12R"))
    )
    (comp (ref "V_LNA")
      (value "TPTP12R")
      (footprint "eagle-import:TP12R")
      (libsource (lib "eagle-import") (part "TPTP12R"))
    )
    (comp (ref "V_PA")
      (value "TPTP12R")
      (footprint "eagle-import:TP12R")
      (libsource (lib "eagle-import") (part "TPTP12R"))
    )
    (comp (ref "V_PA_SRC")
      (value "TPTP12R")
      (footprint "eagle-import:TP12R")
      (libsource (lib "eagle-import") (part "TPTP12R"))
    )
  )
  (nets
    (net (code "1") (name "1V8") (class "Default")
      (node (ref "1V8") (pin "TP") (pinfunction "TP_TP") (pintype "input"))
      (node (ref "C10") (pin "1") (pinfunction "1_1") (pintype "passive"))
      (node (ref "C13") (pin "1") (pinfunction "1_1") (pintype "passive"))
      (node (ref "C9") (pin "1") (pinfunction "1_1") (pintype "passive"))
      (node (ref "Q1") (pin "1") (pinfunction "G_1") (pintype "passive"))
      (node (ref "R14") (pin "2") (pinfunction "2_2") (pintype "passive"))
      (node (ref "R15") (pin "2") (pinfunction "2_2") (pintype "passive"))
      (node (ref "R17") (pin "2") (pinfunction "2_2") (pintype "passive"))
      (node (ref "U5") (pin "5") (pinfunction "OUT_5") (pintype "passive"))
      (node (ref "U8") (pin "P$19") (pinfunction "V18_P$19") (pintype "bidirectional"))
      (node (ref "U8") (pin "P$3") (pinfunction "V18_P$3") (pintype "bidirectional"))
      (node (ref "U8") (pin "P$6") (pinfunction "ON_OFF_P$6") (pintype "bidirectional"))
    )
    (net (code "2") (name "3.3V") (class "Default")
      (node (ref "3V3") (pin "TP") (pinfunction "TP_TP") (pintype "input"))
      (node (ref "C1") (pin "1") (pinfunction "1_1") (pintype "passive"))
      (node (ref "C14") (pin "1") (pinfunction "1_1") (pintype "passive"))
      (node (ref "C15") (pin "1") (pinfunction "1_1") (pintype "passive"))
      (node (ref "C16") (pin "1") (pinfunction "1_1") (pintype "passive"))
      (node (ref "C17") (pin "1") (pinfunction "1_1") (pintype "passive"))
      (node (ref "C26") (pin "1") (pinfunction "1_1") (pintype "passive"))
      (node (ref "C27") (pin "1") (pinfunction "1_1") (pintype "passive"))
      (node (ref "C28") (pin "1") (pinfunction "1_1") (pintype "passive"))
      (node (ref "C8") (pin "1") (pinfunction "1_1") (pintype "passive"))
      (node (ref "L1") (pin "2") (pinfunction "2_2") (pintype "passive"))
      (node (ref "R1") (pin "2") (pinfunction "2_2") (pintype "passive"))
      (node (ref "R16") (pin "2") (pinfunction "2_2") (pintype "passive"))
      (node (ref "R18") (pin "2") (pinfunction "2_2") (pintype "passive"))
      (node (ref "R22") (pin "2") (pinfunction "2_2") (pintype "passive"))
      (node (ref "R8") (pin "2") (pinfunction "2_2") (pintype "passive"))
      (node (ref "U$1") (pin "P$8") (pinfunction "EN_P$8") (pintype "bidirectional"))
      (node (ref "U$1") (pin "P$9") (pinfunction "VCC_P$9") (pintype "bidirectional"))
      (node (ref "U11") (pin "6") (pinfunction "VDD_1_6") (pintype "power_in"))
      (node (ref "U11") (pin "8") (pinfunction "VDD_2_8") (pintype "power_in"))
      (node (ref "U12") (pin "6") (pinfunction "VDD_1_6") (pintype "power_in"))
      (node (ref "U12") (pin "8") (pinfunction "VDD_2_8") (pintype "power_in"))
      (node (ref "U13") (pin "1") (pinfunction "VDD_1") (pintype "bidirectional"))
      (node (ref "U13") (pin "17") (pinfunction "VDD_17") (pintype "bidirectional"))
      (node (ref "U13") (pin "5") (pinfunction "VDDA_5") (pintype "bidirectional"))
      (node (ref "U4") (pin "5") (pinfunction "V+_5") (pintype "bidirectional"))
      (node (ref "U5") (pin "1") (pinfunction "IN_1") (pintype "input"))
      (node (ref "U5") (pin "3") (pinfunction "EN_3") (pintype "input"))
      (node (ref "U6") (pin "4") (pinfunction "S_4") (pintype "passive"))
    )
    (net (code "3") (name "CS1") (class "Default")
      (node (ref "U11") (pin "15") (pinfunction "NSEL_15") (pintype "input"))
      (node (ref "U13") (pin "10") (pinfunction "PA4_10") (pintype "bidirectional"))
    )
    (net (code "4") (name "CS2") (class "Default")
      (node (ref "U12") (pin "15") (pinfunction "NSEL_15") (pintype "input"))
      (node (ref "U13") (pin "30") (pinfunction "PB7_30") (pintype "bidirectional"))
    )
    (net (code "5") (name "GND") (class "Default")
      (node (ref "C1") (pin "2") (pinfunction "2_2") (pintype "passive"))
      (node (ref "C10") (pin "2") (pinfunction "2_2") (pintype "passive"))
      (node (ref "C11") (pin "2") (pinfunction "2_2") (pintype "passive"))
      (node (ref "C13") (pin "2") (pinfunction "2_2") (pintype "passive"))
      (node (ref "C14") (pin "2") (pinfunction "2_2") (pintype "passive"))
      (node (ref "C15") (pin "2") (pinfunction "2_2") (pintype "passive"))
      (node (ref "C16") (pin "2") (pinfunction "2_2") (pintype "passive"))
      (node (ref "C17") (pin "2") (pinfunction "2_2") (pintype "passive"))
      (node (ref "C18") (pin "2") (pinfunction "2_2") (pintype "passive"))
      (node (ref "C21") (pin "2") (pinfunction "2_2") (pintype "passive"))
      (node (ref "C23") (pin "2") (pinfunction "2_2") (pintype "passive"))
      (node (ref "C24") (pin "2") (pinfunction "2_2") (pintype "passive"))
      (node (ref "C25") (pin "2") (pinfunction "2_2") (pintype "passive"))
      (node (ref "C26") (pin "2") (pinfunction "2_2") (pintype "passive"))
      (node (ref "C27") (pin "2") (pinfunction "2_2") (pintype "passive"))
      (node (ref "C28") (pin "2") (pinfunction "2_2") (pintype "passive"))
      (node (ref "C3") (pin "2") (pinfunction "2_2") (pintype "passive"))
      (node (ref "C30") (pin "2") (pinfunction "2_2") (pintype "passive"))
      (node (ref "C31") (pin "2") (pinfunction "2_2") (pintype "passive"))
      (node (ref "C32") (pin "2") (pinfunction "2_2") (pintype "passive"))
      (node (ref "C33") (pin "1") (pinfunction "1_1") (pintype "passive"))
      (node (ref "C34") (pin "2") (pinfunction "2_2") (pintype "passive"))
      (node (ref "C36") (pin "2") (pinfunction "2_2") (pintype "passive"))
      (node (ref "C37") (pin "2") (pinfunction "2_2") (pintype "passive"))
      (node (ref "C39") (pin "2") (pinfunction "2_2") (pintype "passive"))
      (node (ref "C4") (pin "2") (pinfunction "2_2") (pintype "passive"))
      (node (ref "C41") (pin "2") (pinfunction "2_2") (pintype "passive"))
      (node (ref "C42") (pin "2") (pinfunction "2_2") (pintype "passive"))
      (node (ref "C5") (pin "P$1") (pinfunction "P$1_P$1") (pintype "bidirectional"))
      (node (ref "C5") (pin "P$2") (pinfunction "P$2_P$2") (pintype "bidirectional"))
      (node (ref "C6") (pin "2") (pinfunction "2_2") (pintype "passive"))
      (node (ref "C7") (pin "2") (pinfunction "2_2") (pintype "passive"))
      (node (ref "C8") (pin "2") (pinfunction "2_2") (pintype "passive"))
      (node (ref "C9") (pin "2") (pinfunction "2_2") (pintype "passive"))
      (node (ref "D1") (pin "A") (pinfunction "A_A") (pintype "passive"))
      (node (ref "D3") (pin "2") (pinfunction "P$2_2") (pintype "bidirectional"))
      (node (ref "GND1") (pin "TP") (pinfunction "TP_TP") (pintype "input"))
      (node (ref "GND2") (pin "TP") (pinfunction "TP_TP") (pintype "input"))
      (node (ref "J$1") (pin "GND@0") (pinfunction "GND_GND@0") (pintype "bidirectional"))
      (node (ref "J$1") (pin "GND@1") (pinfunction "GND_GND@1") (pintype "bidirectional"))
      (node (ref "J$1") (pin "GND@2") (pinfunction "GND_GND@2") (pintype "bidirectional"))
      (node (ref "J$1") (pin "GND@3") (pinfunction "GND_GND@3") (pintype "bidirectional"))
      (node (ref "J1") (pin "4") (pinfunction "1_4") (pintype "passive"))
      (node (ref "L16") (pin "1") (pinfunction "1_1") (pintype "passive"))
      (node (ref "R12") (pin "1") (pinfunction "1_1") (pintype "passive"))
      (node (ref "R2") (pin "1") (pinfunction "1_1") (pintype "passive"))
      (node (ref "R20") (pin "1") (pinfunction "1_1") (pintype "passive"))
      (node (ref "R23") (pin "2") (pinfunction "2_2") (pintype "passive"))
      (node (ref "R5") (pin "1") (pinfunction "1_1") (pintype "passive"))
      (node (ref "R7") (pin "1") (pinfunction "1_1") (pintype "passive"))
      (node (ref "R9") (pin "1") (pinfunction "1_1") (pintype "passive"))
      (node (ref "S1") (pin "1") (pinfunction "1_1") (pintype "passive"))
      (node (ref "S1") (pin "2") (pinfunction "2_2") (pintype "passive"))
      (node (ref "SWD") (pin "1") (pinfunction "1_1") (pintype "passive"))
      (node (ref "U$1") (pin "P$1") (pinfunction "GND_P$1") (pintype "bidirectional"))
      (node (ref "U$1") (pin "P$10") (pinfunction "GND_P$10") (pintype "bidirectional"))
      (node (ref "U$1") (pin "P$12") (pinfunction "GND_P$12") (pintype "bidirectional"))
      (node (ref "U$1") (pin "P$13") (pinfunction "GND_P$13") (pintype "bidirectional"))
      (node (ref "U$1") (pin "P$3") (pinfunction "GND_P$3") (pintype "bidirectional"))
      (node (ref "U$1") (pin "P$4") (pinfunction "GND_P$4") (pintype "bidirectional"))
      (node (ref "U$1") (pin "P$6") (pinfunction "GND_P$6") (pintype "bidirectional"))
      (node (ref "U1") (pin "2") (pinfunction "GND_2") (pintype "bidirectional"))
      (node (ref "U11") (pin "3") (pinfunction "RXN_3") (pintype "input"))
      (node (ref "U11") (pin "EXP") (pinfunction "PAD_EXP") (pintype "bidirectional"))
      (node (ref "U12") (pin "3") (pinfunction "RXN_3") (pintype "input"))
      (node (ref "U12") (pin "EXP") (pinfunction "PAD_EXP") (pintype "bidirectional"))
      (node (ref "U13") (pin "16") (pinfunction "VSS_16") (pintype "bidirectional"))
      (node (ref "U13") (pin "32") (pinfunction "VSS_32") (pintype "bidirectional"))
      (node (ref "U13") (pin "EXP") (pinfunction "PAD_EXP") (pintype "bidirectional"))
      (node (ref "U14") (pin "2") (pinfunction "GND_2") (pintype "bidirectional"))
      (node (ref "U14") (pin "4") (pinfunction "GND_4") (pintype "bidirectional"))
      (node (ref "U14") (pin "5") (pinfunction "GND_5") (pintype "bidirectional"))
      (node (ref "U2") (pin "1") (pinfunction "G_1") (pintype "passive"))
      (node (ref "U3") (pin "P$4") (pinfunction "GND_P$4") (pintype "bidirectional"))
      (node (ref "U3") (pin "P$7") (pinfunction "GND_P$7") (pintype "bidirectional"))
      (node (ref "U4") (pin "2") (pinfunction "V-_2") (pintype "bidirectional"))
      (node (ref "U5") (pin "2") (pinfunction "GND_2") (pintype "input"))
      (node (ref "U6") (pin "1") (pinfunction "S_1") (pintype "bidirectional"))
      (node (ref "U7") (pin "2") (pinfunction "S_2") (pintype "passive"))
      (node (ref "U7") (pin "2@1") (pinfunction "PAD_2@1") (pintype "bidirectional"))
      (node (ref "U8") (pin "P$10") (pinfunction "GND_P$10") (pintype "bidirectional"))
      (node (ref "U8") (pin "P$2") (pinfunction "GND_P$2") (pintype "bidirectional"))
      (node (ref "U8") (pin "P$20") (pinfunction "GND_P$20") (pintype "bidirectional"))
      (node (ref "U9") (pin "1") (pinfunction "S_1") (pintype "bidirectional"))
      (node (ref "U9") (pin "4") (pinfunction "S_4") (pintype "bidirectional"))
      (node (ref "X1") (pin "2") (pinfunction "G2_2") (pintype "power_in"))
      (node (ref "X1") (pin "4") (pinfunction "G1_4") (pintype "power_in"))
      (node (ref "X2") (pin "2") (pinfunction "G2_2") (pintype "power_in"))
      (node (ref "X2") (pin "4") (pinfunction "G1_4") (pintype "power_in"))
    )
    (net (code "6") (name "GNSS_1PPS") (class "Default")
      (node (ref "U8") (pin "P$11") (pinfunction "TM_P$11") (pintype "bidirectional"))
      (node (ref "U9") (pin "5") (pinfunction "G_5") (pintype "bidirectional"))
    )
    (net (code "7") (name "GNSS_NMEA_RX") (class "Default")
      (node (ref "Q1") (pin "3") (pinfunction "D_3") (pintype "passive"))
      (node (ref "R16") (pin "1") (pinfunction "1_1") (pintype "passive"))
      (node (ref "U13") (pin "9") (pinfunction "PA3_9") (pintype "bidirectional"))
    )
    (net (code "8") (name "GNSS_UART_TX") (class "Default")
      (node (ref "Q1") (pin "2") (pinfunction "S_2") (pintype "passive"))
      (node (ref "R15") (pin "1") (pinfunction "1_1") (pintype "passive"))
      (node (ref "U8") (pin "P$15") (pinfunction "TX_P$15") (pintype "bidirectional"))
    )
    (net (code "9") (name "LNA_IN") (class "Default")
      (node (ref "L14") (pin "1") (pinfunction "1_1") (pintype "passive"))
      (node (ref "U$1") (pin "P$11") (pinfunction "RF2_P$11") (pintype "bidirectional"))
    )
    (net (code "10") (name "LNA_OUT") (class "Default")
      (node (ref "C19") (pin "2") (pinfunction "2_2") (pintype "passive"))
      (node (ref "U11") (pin "2") (pinfunction "RXP_2") (pintype "input"))
      (node (ref "U12") (pin "2") (pinfunction "RXP_2") (pintype "input"))
    )
    (net (code "11") (name "MCU_GNSS_1PPS") (class "Default")
      (node (ref "R18") (pin "1") (pinfunction "1_1") (pintype "passive"))
      (node (ref "U13") (pin "8") (pinfunction "PA2_8") (pintype "bidirectional"))
      (node (ref "U9") (pin "6") (pinfunction "D_6") (pintype "bidirectional"))
    )
    (net (code "12") (name "MCU_UART_RX") (class "Default")
      (node (ref "J1") (pin "3") (pinfunction "1_3") (pintype "passive"))
      (node (ref "RX") (pin "TP") (pinfunction "TP_TP") (pintype "input"))
      (node (ref "U13") (pin "20") (pinfunction "PA10_20") (pintype "bidirectional"))
    )
    (net (code "13") (name "MCU_UART_TX") (class "Default")
      (node (ref "J1") (pin "2") (pinfunction "1_2") (pintype "passive"))
      (node (ref "TX") (pin "TP") (pinfunction "TP_TP") (pintype "input"))
      (node (ref "U13") (pin "19") (pinfunction "PA9_19") (pintype "bidirectional"))
    )
    (net (code "14") (name "MISO") (class "Default")
      (node (ref "U11") (pin "13") (pinfunction "SDO_13") (pintype "output"))
      (node (ref "U12") (pin "13") (pinfunction "SDO_13") (pintype "output"))
      (node (ref "U13") (pin "12") (pinfunction "PA6_12") (pintype "bidirectional"))
    )
    (net (code "15") (name "MOSI") (class "Default")
      (node (ref "U11") (pin "14") (pinfunction "SDI_14") (pintype "input"))
      (node (ref "U12") (pin "14") (pinfunction "SDI_14") (pintype "input"))
      (node (ref "U13") (pin "13") (pinfunction "PA7_13") (pintype "bidirectional"))
    )
    (net (code "16") (name "NRST") (class "Default")
      (node (ref "C41") (pin "1") (pinfunction "1_1") (pintype "passive"))
      (node (ref "NRST") (pin "TP") (pinfunction "TP_TP") (pintype "input"))
      (node (ref "S1") (pin "3") (pinfunction "3_3") (pintype "passive"))
      (node (ref "S1") (pin "4") (pinfunction "4_4") (pintype "passive"))
      (node (ref "SWD") (pin "2") (pinfunction "2_2") (pintype "passive"))
      (node (ref "U13") (pin "4") (pinfunction "NRST_4") (pintype "bidirectional"))
    )
    (net (code "17") (name "Net-(C11-Pad1)") (class "Default")
      (node (ref "C11") (pin "1") (pinfunction "1_1") (pintype "passive"))
      (node (ref "C32") (pin "1") (pinfunction "1_1") (pintype "passive"))
      (node (ref "C34") (pin "1") (pinfunction "1_1") (pintype "passive"))
      (node (ref "L3") (pin "2") (pinfunction "2_2") (pintype "passive"))
      (node (ref "L8") (pin "1") (pinfunction "1_1") (pintype "passive"))
      (node (ref "R13") (pin "2") (pinfunction "2_2") (pintype "passive"))
    )
    (net (code "18") (name "Net-(C20-Pad1)") (class "Default")
      (node (ref "C20") (pin "1") (pinfunction "1_1") (pintype "passive"))
      (node (ref "L15") (pin "2") (pinfunction "2_2") (pintype "passive"))
    )
    (net (code "19") (name "Net-(C21-Pad1)") (class "Default")
      (node (ref "C21") (pin "1") (pinfunction "1_1") (pintype "passive"))
      (node (ref "L5") (pin "1") (pinfunction "1_1") (pintype "passive"))
      (node (ref "R22") (pin "1") (pinfunction "1_1") (pintype "passive"))
    )
    (net (code "20") (name "Net-(C22-Pad2)") (class "Default")
      (node (ref "C22") (pin "2") (pinfunction "2_2") (pintype "passive"))
      (node (ref "L6") (pin "1") (pinfunction "1_1") (pintype "passive"))
    )
    (net (code "21") (name "Net-(C23-Pad1)") (class "Default")
      (node (ref "C23") (pin "1") (pinfunction "1_1") (pintype "passive"))
      (node (ref "L6") (pin "2") (pinfunction "2_2") (pintype "passive"))
      (node (ref "L7") (pin "1") (pinfunction "1_1") (pintype "passive"))
    )
    (net (code "22") (name "Net-(C24-Pad1)") (class "Default")
      (node (ref "C24") (pin "1") (pinfunction "1_1") (pintype "passive"))
      (node (ref "L11") (pin "1") (pinfunction "1_1") (pintype "passive"))
      (node (ref "L7") (pin "2") (pinfunction "2_2") (pintype "passive"))
    )
    (net (code "23") (name "Net-(C25-Pad1)") (class "Default")
      (node (ref "C25") (pin "1") (pinfunction "1_1") (pintype "passive"))
      (node (ref "L11") (pin "2") (pinfunction "2_2") (pintype "passive"))
      (node (ref "L12") (pin "1") (pinfunction "1_1") (pintype "passive"))
    )
    (net (code "24") (name "Net-(C29-Pad2)") (class "Default")
      (node (ref "C29") (pin "2") (pinfunction "2_2") (pintype "passive"))
      (node (ref "C30") (pin "1") (pinfunction "1_1") (pintype "passive"))
      (node (ref "C31") (pin "1") (pinfunction "1_1") (pintype "passive"))
      (node (ref "L3") (pin "1") (pinfunction "1_1") (pintype "passive"))
    )
    (net (code "25") (name "Net-(C33-Pad2)") (class "Default")
      (node (ref "C33") (pin "2") (pinfunction "2_2") (pintype "passive"))
      (node (ref "C35") (pin "1") (pinfunction "1_1") (pintype "passive"))
      (node (ref "C40") (pin "2") (pinfunction "2_2") (pintype "passive"))
      (node (ref "L16") (pin "2") (pinfunction "2_2") (pintype "passive"))
    )
    (net (code "26") (name "Net-(C35-Pad2)") (class "Default")
      (node (ref "C35") (pin "2") (pinfunction "2_2") (pintype "passive"))
      (node (ref "L14") (pin "2") (pinfunction "2_2") (pintype "passive"))
    )
    (net (code "27") (name "Net-(C36-Pad1)") (class "Default")
      (node (ref "C36") (pin "1") (pinfunction "1_1") (pintype "passive"))
      (node (ref "L10") (pin "1") (pinfunction "1_1") (pintype "passive"))
      (node (ref "L9") (pin "2") (pinfunction "2_2") (pintype "passive"))
    )
    (net (code "28") (name "Net-(C40-Pad1)") (class "Default")
      (node (ref "C40") (pin "1") (pinfunction "1_1") (pintype "passive"))
      (node (ref "L15") (pin "1") (pinfunction "1_1") (pintype "passive"))
    )
    (net (code "29") (name "Net-(C42-Pad1)") (class "Default")
      (node (ref "C42") (pin "1") (pinfunction "1_1") (pintype "passive"))
      (node (ref "C44") (pin "1") (pinfunction "1_1") (pintype "passive"))
      (node (ref "L10") (pin "2") (pinfunction "2_2") (pintype "passive"))
    )
    (net (code "30") (name "Net-(D2-PadA)") (class "Default")
      (node (ref "D2") (pin "A") (pinfunction "A_A") (pintype "passive"))
      (node (ref "R3") (pin "2") (pinfunction "2_2") (pintype "passive"))
    )
    (net (code "31") (name "Net-(D3-P$1)") (class "Default")
      (node (ref "D3") (pin "1") (pinfunction "P$1_1") (pintype "bidirectional"))
      (node (ref "J1") (pin "1") (pinfunction "1_1") (pintype "passive"))
      (node (ref "U2") (pin "3") (pinfunction "D_3") (pintype "passive"))
      (node (ref "V_IN") (pin "TP") (pinfunction "TP_TP") (pintype "input"))
    )
    (net (code "32") (name "Net-(J$1-SIGNAL)") (class "Default")
      (node (ref "J$1") (pin "SIG") (pinfunction "SIGNAL_SIG") (pintype "bidirectional"))
      (node (ref "U$1") (pin "P$2") (pinfunction "RF1_P$2") (pintype "bidirectional"))
    )
    (net (code "33") (name "Net-(R11-Pad1)") (class "Default")
      (node (ref "R11") (pin "1") (pinfunction "1_1") (pintype "passive"))
      (node (ref "R12") (pin "2") (pinfunction "2_2") (pintype "passive"))
      (node (ref "R13") (pin "1") (pinfunction "1_1") (pintype "passive"))
    )
    (net (code "34") (name "Net-(U$1-CTRL)") (class "Default")
      (node (ref "R19") (pin "1") (pinfunction "1_1") (pintype "passive"))
      (node (ref "R20") (pin "2") (pinfunction "2_2") (pintype "passive"))
      (node (ref "U$1") (pin "P$7") (pinfunction "CTRL_P$7") (pintype "bidirectional"))
    )
    (net (code "35") (name "Net-(U1-BS)") (class "Default")
      (node (ref "C2") (pin "1") (pinfunction "1_1") (pintype "passive"))
      (node (ref "U1") (pin "1") (pinfunction "BS_1") (pintype "bidirectional"))
    )
    (net (code "36") (name "Net-(U1-EN)") (class "Default")
      (node (ref "C3") (pin "1") (pinfunction "1_1") (pintype "passive"))
      (node (ref "L2") (pin "2") (pinfunction "2_2") (pintype "passive"))
      (node (ref "U1") (pin "4") (pinfunction "EN_4") (pintype "bidirectional"))
      (node (ref "U1") (pin "5") (pinfunction "IN_5") (pintype "bidirectional"))
    )
    (net (code "37") (name "Net-(U1-FB)") (class "Default")
      (node (ref "R1") (pin "1") (pinfunction "1_1") (pintype "passive"))
      (node (ref "R2") (pin "2") (pinfunction "2_2") (pintype "passive"))
      (node (ref "U1") (pin "3") (pinfunction "FB_3") (pintype "bidirectional"))
    )
    (net (code "38") (name "Net-(U1-SW)") (class "Default")
      (node (ref "C2") (pin "2") (pinfunction "2_2") (pintype "passive"))
      (node (ref "D1") (pin "C") (pinfunction "C_C") (pintype "passive"))
      (node (ref "L1") (pin "1") (pinfunction "1_1") (pintype "passive"))
      (node (ref "U1") (pin "6") (pinfunction "SW_6") (pintype "bidirectional"))
    )
    (net (code "39") (name "Net-(U3-ADJ)") (class "Default")
      (node (ref "R4") (pin "1") (pinfunction "1_1") (pintype "passive"))
      (node (ref "R5") (pin "2") (pinfunction "2_2") (pintype "passive"))
      (node (ref "U3") (pin "P$2") (pinfunction "ADJ_P$2") (pintype "bidirectional"))
    )
    (net (code "40") (name "Net-(U4-IN+)") (class "Default")
      (node (ref "R6") (pin "1") (pinfunction "1_1") (pintype "passive"))
      (node (ref "R7") (pin "2") (pinfunction "2_2") (pintype "passive"))
      (node (ref "U4") (pin "1") (pinfunction "IN+_1") (pintype "bidirectional"))
    )
    (net (code "41") (name "Net-(U6A-D)") (class "Default")
      (node (ref "R8") (pin "1") (pinfunction "1_1") (pintype "passive"))
      (node (ref "U6") (pin "5") (pinfunction "G_5") (pintype "passive"))
      (node (ref "U6") (pin "6") (pinfunction "D_6") (pintype "bidirectional"))
    )
    (net (code "42") (name "Net-(U7-D)") (class "Default")
      (node (ref "C37") (pin "1") (pinfunction "1_1") (pintype "passive"))
      (node (ref "C39") (pin "1") (pinfunction "1_1") (pintype "passive"))
      (node (ref "L4") (pin "2") (pinfunction "2_2") (pintype "passive"))
      (node (ref "L9") (pin "1") (pinfunction "1_1") (pintype "passive"))
      (node (ref "U7") (pin "3") (pinfunction "D_3") (pintype "passive"))
    )
    (net (code "43") (name "Net-(U7-G)") (class "Default")
      (node (ref "L8") (pin "2") (pinfunction "2_2") (pintype "passive"))
      (node (ref "U7") (pin "1") (pinfunction "G_1") (pintype "passive"))
    )
    (net (code "44") (name "Net-(U8-GPIO6)") (class "Default")
      (node (ref "R14") (pin "1") (pinfunction "1_1") (pintype "passive"))
      (node (ref "U8") (pin "P$13") (pinfunction "GPIO6_P$13") (pintype "bidirectional"))
    )
    (net (code "45") (name "Net-(U8-RF_IN)") (class "Default")
      (node (ref "C12") (pin "2") (pinfunction "2_2") (pintype "passive"))
      (node (ref "U8") (pin "P$1") (pinfunction "RF_IN_P$1") (pintype "bidirectional"))
    )
    (net (code "46") (name "Net-(U9A-D)") (class "Default")
      (node (ref "R17") (pin "1") (pinfunction "1_1") (pintype "passive"))
      (node (ref "U9") (pin "2") (pinfunction "G_2") (pintype "bidirectional"))
      (node (ref "U9") (pin "3") (pinfunction "D_3") (pintype "bidirectional"))
    )
    (net (code "47") (name "Net-(U10-RF)") (class "Default")
      (node (ref "C12") (pin "1") (pinfunction "1_1") (pintype "passive"))
      (node (ref "U10") (pin "P$1") (pinfunction "RF_P$1") (pintype "bidirectional"))
    )
    (net (code "48") (name "Net-(U11-TX)") (class "Default")
      (node (ref "C22") (pin "1") (pinfunction "1_1") (pintype "passive"))
      (node (ref "L5") (pin "2") (pinfunction "2_2") (pintype "passive"))
      (node (ref "U11") (pin "4") (pinfunction "TX_4") (pintype "output"))
    )
    (net (code "49") (name "Net-(U11-XIN)") (class "Default")
      (node (ref "U11") (pin "17") (pinfunction "XIN_17") (pintype "input"))
      (node (ref "X1") (pin "3") (pinfunction "X2_3") (pintype "bidirectional"))
    )
    (net (code "50") (name "Net-(U11-XOUT)") (class "Default")
      (node (ref "U11") (pin "16") (pinfunction "XOUT_16") (pintype "bidirectional"))
      (node (ref "X1") (pin "1") (pinfunction "X1_1") (pintype "bidirectional"))
    )
    (net (code "51") (name "Net-(U12-XIN)") (class "Default")
      (node (ref "U12") (pin "17") (pinfunction "XIN_17") (pintype "input"))
      (node (ref "X2") (pin "3") (pinfunction "X2_3") (pintype "bidirectional"))
    )
    (net (code "52") (name "Net-(U12-XOUT)") (class "Default")
      (node (ref "U12") (pin "16") (pinfunction "XOUT_16") (pintype "bidirectional"))
      (node (ref "X2") (pin "1") (pinfunction "X1_1") (pintype "bidirectional"))
    )
    (net (code "53") (name "Net-(U13-BOOT0)") (class "Default")
      (node (ref "R23") (pin "1") (pinfunction "1_1") (pintype "passive"))
      (node (ref "U13") (pin "31") (pinfunction "BOOT0_31") (pintype "bidirectional"))
    )
    (net (code "54") (name "Net-(U14-IN)") (class "Default")
      (node (ref "C20") (pin "2") (pinfunction "2_2") (pintype "passive"))
      (node (ref "U14") (pin "6") (pinfunction "IN_6") (pintype "bidirectional"))
    )
    (net (code "55") (name "Net-(U14-OUT)") (class "Default")
      (node (ref "C19") (pin "1") (pinfunction "1_1") (pintype "passive"))
      (node (ref "U14") (pin "3") (pinfunction "OUT_3") (pintype "bidirectional"))
    )
    (net (code "56") (name "Net-(U14-VCC)") (class "Default")
      (node (ref "C18") (pin "1") (pinfunction "1_1") (pintype "passive"))
      (node (ref "R21") (pin "2") (pinfunction "2_2") (pintype "passive"))
      (node (ref "U14") (pin "1") (pinfunction "VCC_1") (pintype "bidirectional"))
    )
    (net (code "57") (name "PA_IN") (class "Default")
      (node (ref "C29") (pin "1") (pinfunction "1_1") (pintype "passive"))
      (node (ref "L12") (pin "2") (pinfunction "2_2") (pintype "passive"))
    )
    (net (code "58") (name "PA_OUT") (class "Default")
      (node (ref "C44") (pin "2") (pinfunction "2_2") (pintype "passive"))
      (node (ref "U$1") (pin "P$5") (pinfunction "RF3_P$5") (pintype "bidirectional"))
    )
    (net (code "59") (name "RFSW_CTRL") (class "Default")
      (node (ref "R19") (pin "2") (pinfunction "2_2") (pintype "passive"))
      (node (ref "R9") (pin "2") (pinfunction "2_2") (pintype "passive"))
      (node (ref "U13") (pin "2") (pinfunction "OSC_IN/PC14_2") (pintype "bidirectional"))
      (node (ref "U6") (pin "2") (pinfunction "G_2") (pintype "bidirectional"))
    )
    (net (code "60") (name "RX_IC_CLK") (class "Default")
      (node (ref "U12") (pin "20") (pinfunction "GPIO3_20") (pintype "bidirectional"))
      (node (ref "U13") (pin "26") (pinfunction "PB3_26") (pintype "bidirectional"))
    )
    (net (code "61") (name "RX_IC_DATA") (class "Default")
      (node (ref "U12") (pin "10") (pinfunction "GPIO1_10") (pintype "bidirectional"))
      (node (ref "U13") (pin "27") (pinfunction "PB4_27") (pintype "bidirectional"))
    )
    (net (code "62") (name "SCK") (class "Default")
      (node (ref "U11") (pin "12") (pinfunction "SCLK_12") (pintype "input"))
      (node (ref "U12") (pin "12") (pinfunction "SCLK_12") (pintype "input"))
      (node (ref "U13") (pin "11") (pinfunction "PA5_11") (pintype "bidirectional"))
    )
    (net (code "63") (name "SDN1") (class "Default")
      (node (ref "U11") (pin "1") (pinfunction "SDN_1") (pintype "input"))
      (node (ref "U13") (pin "14") (pinfunction "PB0_14") (pintype "bidirectional"))
    )
    (net (code "64") (name "SDN2") (class "Default")
      (node (ref "U12") (pin "1") (pinfunction "SDN_1") (pintype "input"))
      (node (ref "U13") (pin "25") (pinfunction "PA15_25") (pintype "bidirectional"))
    )
    (net (code "65") (name "SWCLK") (class "Default")
      (node (ref "SWCLK") (pin "TP") (pinfunction "TP_TP") (pintype "input"))
      (node (ref "SWD") (pin "3") (pinfunction "3_3") (pintype "passive"))
      (node (ref "U13") (pin "24") (pinfunction "PA14_24") (pintype "bidirectional"))
    )
    (net (code "66") (name "SWDIO") (class "Default")
      (node (ref "SWD") (pin "4") (pinfunction "4_4") (pintype "passive"))
      (node (ref "SWDIO") (pin "TP") (pinfunction "TP_TP") (pintype "input"))
      (node (ref "U13") (pin "23") (pinfunction "PA13_23") (pintype "bidirectional"))
    )
    (net (code "67") (name "TRX_IC_CLOCK") (class "Default")
      (node (ref "U11") (pin "19") (pinfunction "GPIO2_19") (pintype "bidirectional"))
      (node (ref "U13") (pin "7") (pinfunction "PA1_7") (pintype "bidirectional"))
    )
    (net (code "68") (name "TRX_IC_DATA") (class "Default")
      (node (ref "U11") (pin "10") (pinfunction "GPIO1_10") (pintype "bidirectional"))
      (node (ref "U13") (pin "15") (pinfunction "PB1_15") (pintype "bidirectional"))
    )
    (net (code "69") (name "TX_CTRL") (class "Default")
      (node (ref "R11") (pin "2") (pinfunction "2_2") (pintype "passive"))
      (node (ref "U13") (pin "29") (pinfunction "PB6_29") (pintype "bidirectional"))
    )
    (net (code "70") (name "V_BAT") (class "Default")
      (node (ref "C4") (pin "1") (pinfunction "1_1") (pintype "passive"))
      (node (ref "L2") (pin "1") (pinfunction "1_1") (pintype "passive"))
      (node (ref "R3") (pin "1") (pinfunction "1_1") (pintype "passive"))
      (node (ref "U2") (pin "2") (pinfunction "S_2") (pintype "passive"))
    )
    (net (code "71") (name "V_LNA") (class "Default")
      (node (ref "R21") (pin "1") (pinfunction "1_1") (pintype "passive"))
      (node (ref "U6") (pin "3") (pinfunction "D_3") (pintype "passive"))
      (node (ref "V_LNA") (pin "TP") (pinfunction "TP_TP") (pintype "input"))
    )
    (net (code "72") (name "V_PA") (class "Default")
      (node (ref "C7") (pin "1") (pinfunction "1_1") (pintype "passive"))
      (node (ref "L4") (pin "1") (pinfunction "1_1") (pintype "passive"))
      (node (ref "R4") (pin "2") (pinfunction "2_2") (pintype "passive"))
      (node (ref "U3") (pin "P$1") (pinfunction "VOUT_P$1") (pintype "bidirectional"))
      (node (ref "V_PA") (pin "TP") (pinfunction "TP_TP") (pintype "input"))
    )
    (net (code "73") (name "V_PA_SRC") (class "Default")
      (node (ref "C5") (pin "P$3") (pinfunction "P$3_P$3") (pintype "bidirectional"))
      (node (ref "C6") (pin "1") (pinfunction "1_1") (pintype "passive"))
      (node (ref "D2") (pin "C") (pinfunction "C_C") (pintype "passive"))
      (node (ref "R6") (pin "2") (pinfunction "2_2") (pintype "passive"))
      (node (ref "U3") (pin "P$5") (pinfunction "EN_P$5") (pintype "bidirectional"))
      (node (ref "U3") (pin "P$6") (pinfunction "VIN_P$6") (pintype "bidirectional"))
      (node (ref "V_PA_SRC") (pin "TP") (pinfunction "TP_TP") (pintype "input"))
    )
    (net (code "74") (name "V_PA_SRC_DIV") (class "Default")
      (node (ref "U13") (pin "6") (pinfunction "PA0_6") (pintype "bidirectional"))
      (node (ref "U4") (pin "3") (pinfunction "IN-_3") (pintype "bidirectional"))
      (node (ref "U4") (pin "4") (pinfunction "OUT_4") (pintype "bidirectional"))
    )
    (net (code "75") (name "unconnected-(U3-PG-PadP$3)") (class "Default")
      (node (ref "U3") (pin "P$3") (pinfunction "PG_P$3") (pintype "bidirectional"))
    )
    (net (code "76") (name "unconnected-(U5-BP-Pad4)") (class "Default")
      (node (ref "U5") (pin "4") (pinfunction "BP_4") (pintype "input"))
    )
    (net (code "77") (name "unconnected-(U8-BOOTSEL-PadP$9)") (class "Default")
      (node (ref "U8") (pin "P$9") (pinfunction "BOOTSEL_P$9") (pintype "bidirectional"))
    )
    (net (code "78") (name "unconnected-(U8-GPIO0-PadP$18)") (class "Default")
      (node (ref "U8") (pin "P$18") (pinfunction "GPIO0_P$18") (pintype "bidirectional"))
    )
    (net (code "79") (name "unconnected-(U8-GPIO1-PadP$17)") (class "Default")
      (node (ref "U8") (pin "P$17") (pinfunction "GPIO1_P$17") (pintype "bidirectional"))
    )
    (net (code "80") (name "unconnected-(U8-GPIO7-PadP$12)") (class "Default")
      (node (ref "U8") (pin "P$12") (pinfunction "GPIO7_P$12") (pintype "bidirectional"))
    )
    (net (code "81") (name "unconnected-(U8-GPIO8-PadP$5)") (class "Default")
      (node (ref "U8") (pin "P$5") (pinfunction "GPIO8_P$5") (pintype "bidirectional"))
    )
    (net (code "82") (name "unconnected-(U8-NC-PadP$4)") (class "Default")
      (node (ref "U8") (pin "P$4") (pinfunction "NC_P$4") (pintype "bidirectional"))
    )
    (net (code "83") (name "unconnected-(U8-NC-PadP$16)") (class "Default")
      (node (ref "U8") (pin "P$16") (pinfunction "NC_P$16") (pintype "bidirectional"))
    )
    (net (code "84") (name "unconnected-(U8-NRESET-PadP$8)") (class "Default")
      (node (ref "U8") (pin "P$8") (pinfunction "NRESET_P$8") (pintype "bidirectional"))
    )
    (net (code "85") (name "unconnected-(U8-RX-PadP$14)") (class "Default")
      (node (ref "U8") (pin "P$14") (pinfunction "RX_P$14") (pintype "bidirectional"))
    )
    (net (code "86") (name "unconnected-(U8-SYS_ON-PadP$7)") (class "Default")
      (node (ref "U8") (pin "P$7") (pinfunction "SYS_ON_P$7") (pintype "bidirectional"))
    )
    (net (code "87") (name "unconnected-(U10-PAD-PadP$2)") (class "Default")
      (node (ref "U10") (pin "P$2") (pinfunction "PAD_P$2") (pintype "bidirectional"))
    )
    (net (code "88") (name "unconnected-(U11-GNDX-Pad18)") (class "Default")
      (node (ref "U11") (pin "18") (pinfunction "GNDX_18") (pintype "bidirectional"))
    )
    (net (code "89") (name "unconnected-(U11-GPIO0-Pad9)") (class "Default")
      (node (ref "U11") (pin "9") (pinfunction "GPIO0_9") (pintype "bidirectional"))
    )
    (net (code "90") (name "unconnected-(U11-GPIO3-Pad20)") (class "Default")
      (node (ref "U11") (pin "20") (pinfunction "GPIO3_20") (pintype "bidirectional"))
    )
    (net (code "91") (name "unconnected-(U11-NIRQ-Pad11)") (class "Default")
      (node (ref "U11") (pin "11") (pinfunction "NIRQ_11") (pintype "bidirectional"))
    )
    (net (code "92") (name "unconnected-(U11-TXRAMP-Pad7)") (class "Default")
      (node (ref "U11") (pin "7") (pinfunction "TXRAMP_7") (pintype "bidirectional"))
    )
    (net (code "93") (name "unconnected-(U12-GNDX-Pad18)") (class "Default")
      (node (ref "U12") (pin "18") (pinfunction "GNDX_18") (pintype "bidirectional"))
    )
    (net (code "94") (name "unconnected-(U12-GPIO0-Pad9)") (class "Default")
      (node (ref "U12") (pin "9") (pinfunction "GPIO0_9") (pintype "bidirectional"))
    )
    (net (code "95") (name "unconnected-(U12-GPIO2-Pad19)") (class "Default")
      (node (ref "U12") (pin "19") (pinfunction "GPIO2_19") (pintype "bidirectional"))
    )
    (net (code "96") (name "unconnected-(U12-NIRQ-Pad11)") (class "Default")
      (node (ref "U12") (pin "11") (pinfunction "NIRQ_11") (pintype "bidirectional"))
    )
    (net (code "97") (name "unconnected-(U12-TX-Pad4)") (class "Default")
      (node (ref "U12") (pin "4") (pinfunction "TX_4") (pintype "output"))
    )
    (net (code "98") (name "unconnected-(U12-TXRAMP-Pad7)") (class "Default")
      (node (ref "U12") (pin "7") (pinfunction "TXRAMP_7") (pintype "bidirectional"))
    )
    (net (code "99") (name "unconnected-(U13-OSC_OUT{slash}PC15-Pad3)") (class "Default")
      (node (ref "U13") (pin "3") (pinfunction "OSC_OUT/PC15_3") (pintype "bidirectional"))
    )
    (net (code "100") (name "unconnected-(U13-PA8-Pad18)") (class "Default")
      (node (ref "U13") (pin "18") (pinfunction "PA8_18") (pintype "bidirectional"))
    )
    (net (code "101") (name "unconnected-(U13-PA11-Pad21)") (class "Default")
      (node (ref "U13") (pin "21") (pinfunction "PA11_21") (pintype "bidirectional"))
    )
    (net (code "102") (name "unconnected-(U13-PA12-Pad22)") (class "Default")
      (node (ref "U13") (pin "22") (pinfunction "PA12_22") (pintype "bidirectional"))
    )
    (net (code "103") (name "unconnected-(U13-PB5-Pad28)") (class "Default")
      (node (ref "U13") (pin "28") (pinfunction "PB5_28") (pintype "bidirectional"))
    )
  )
)
